# module_special_reg_ctrl.net
KiCad netlist of a schematic drawn in EAGLE
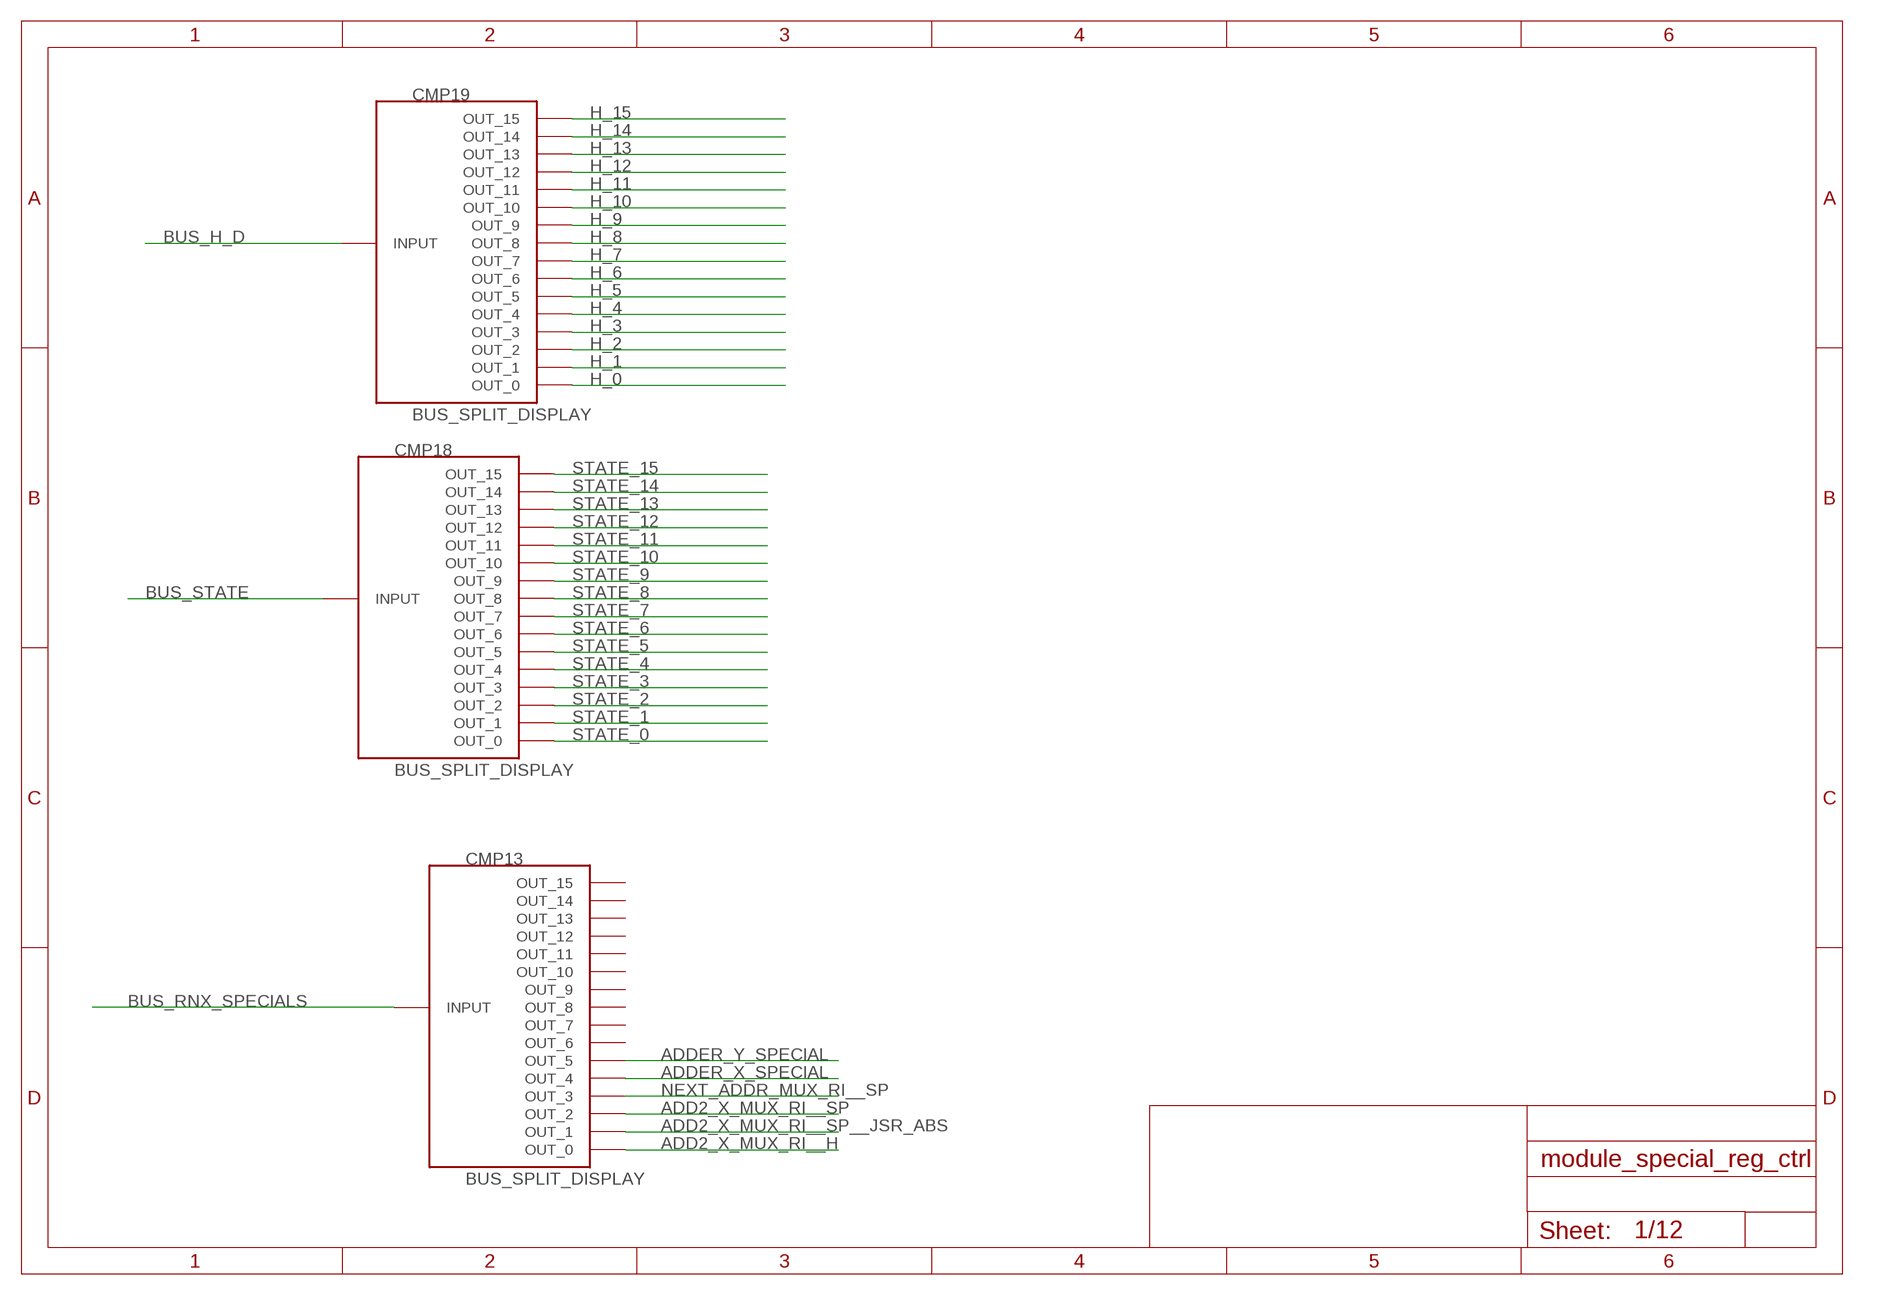
[diagram p0: schematic, sheet 1]
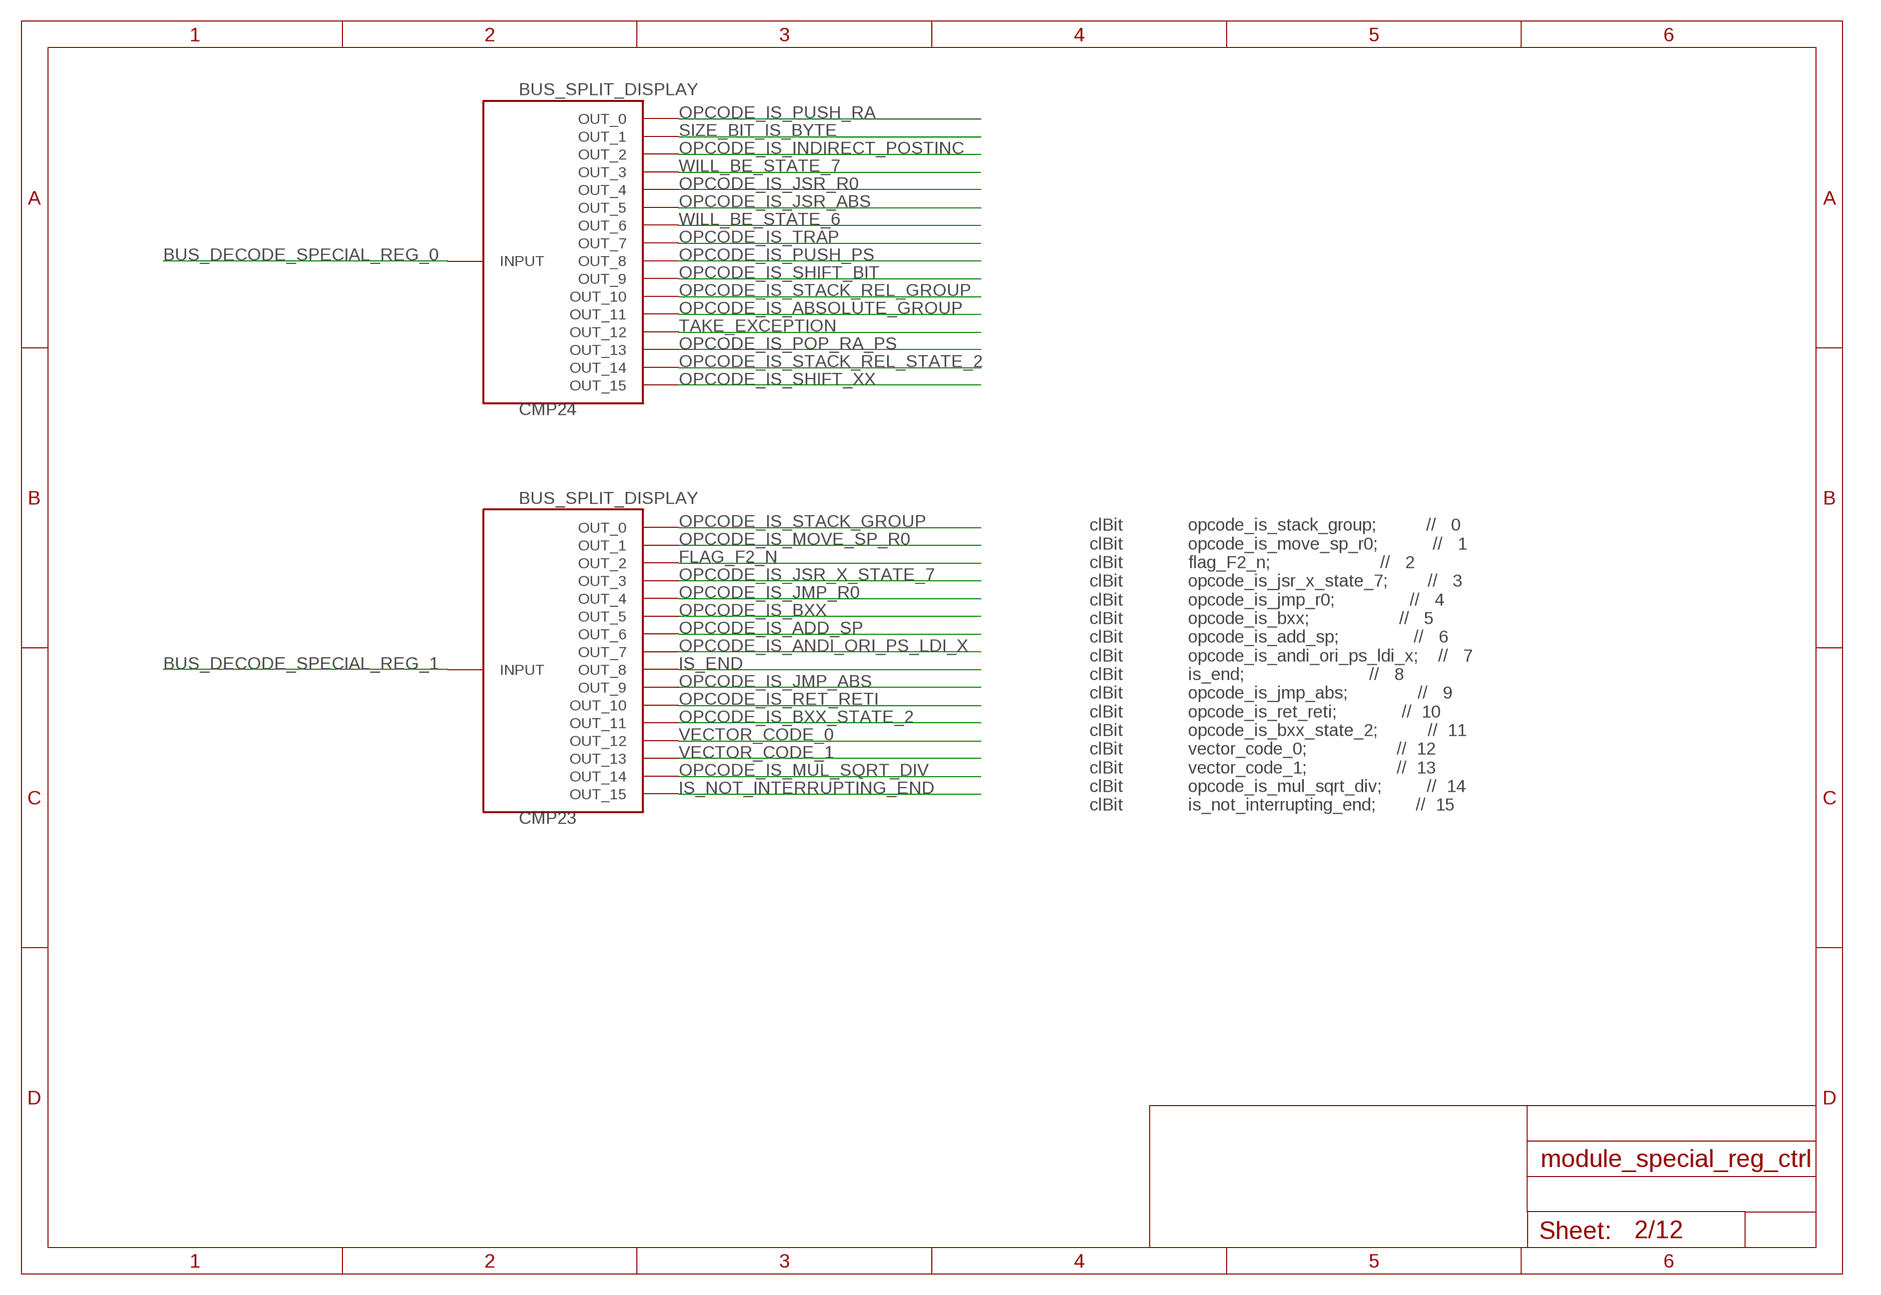
[diagram p1: schematic, sheet 2]
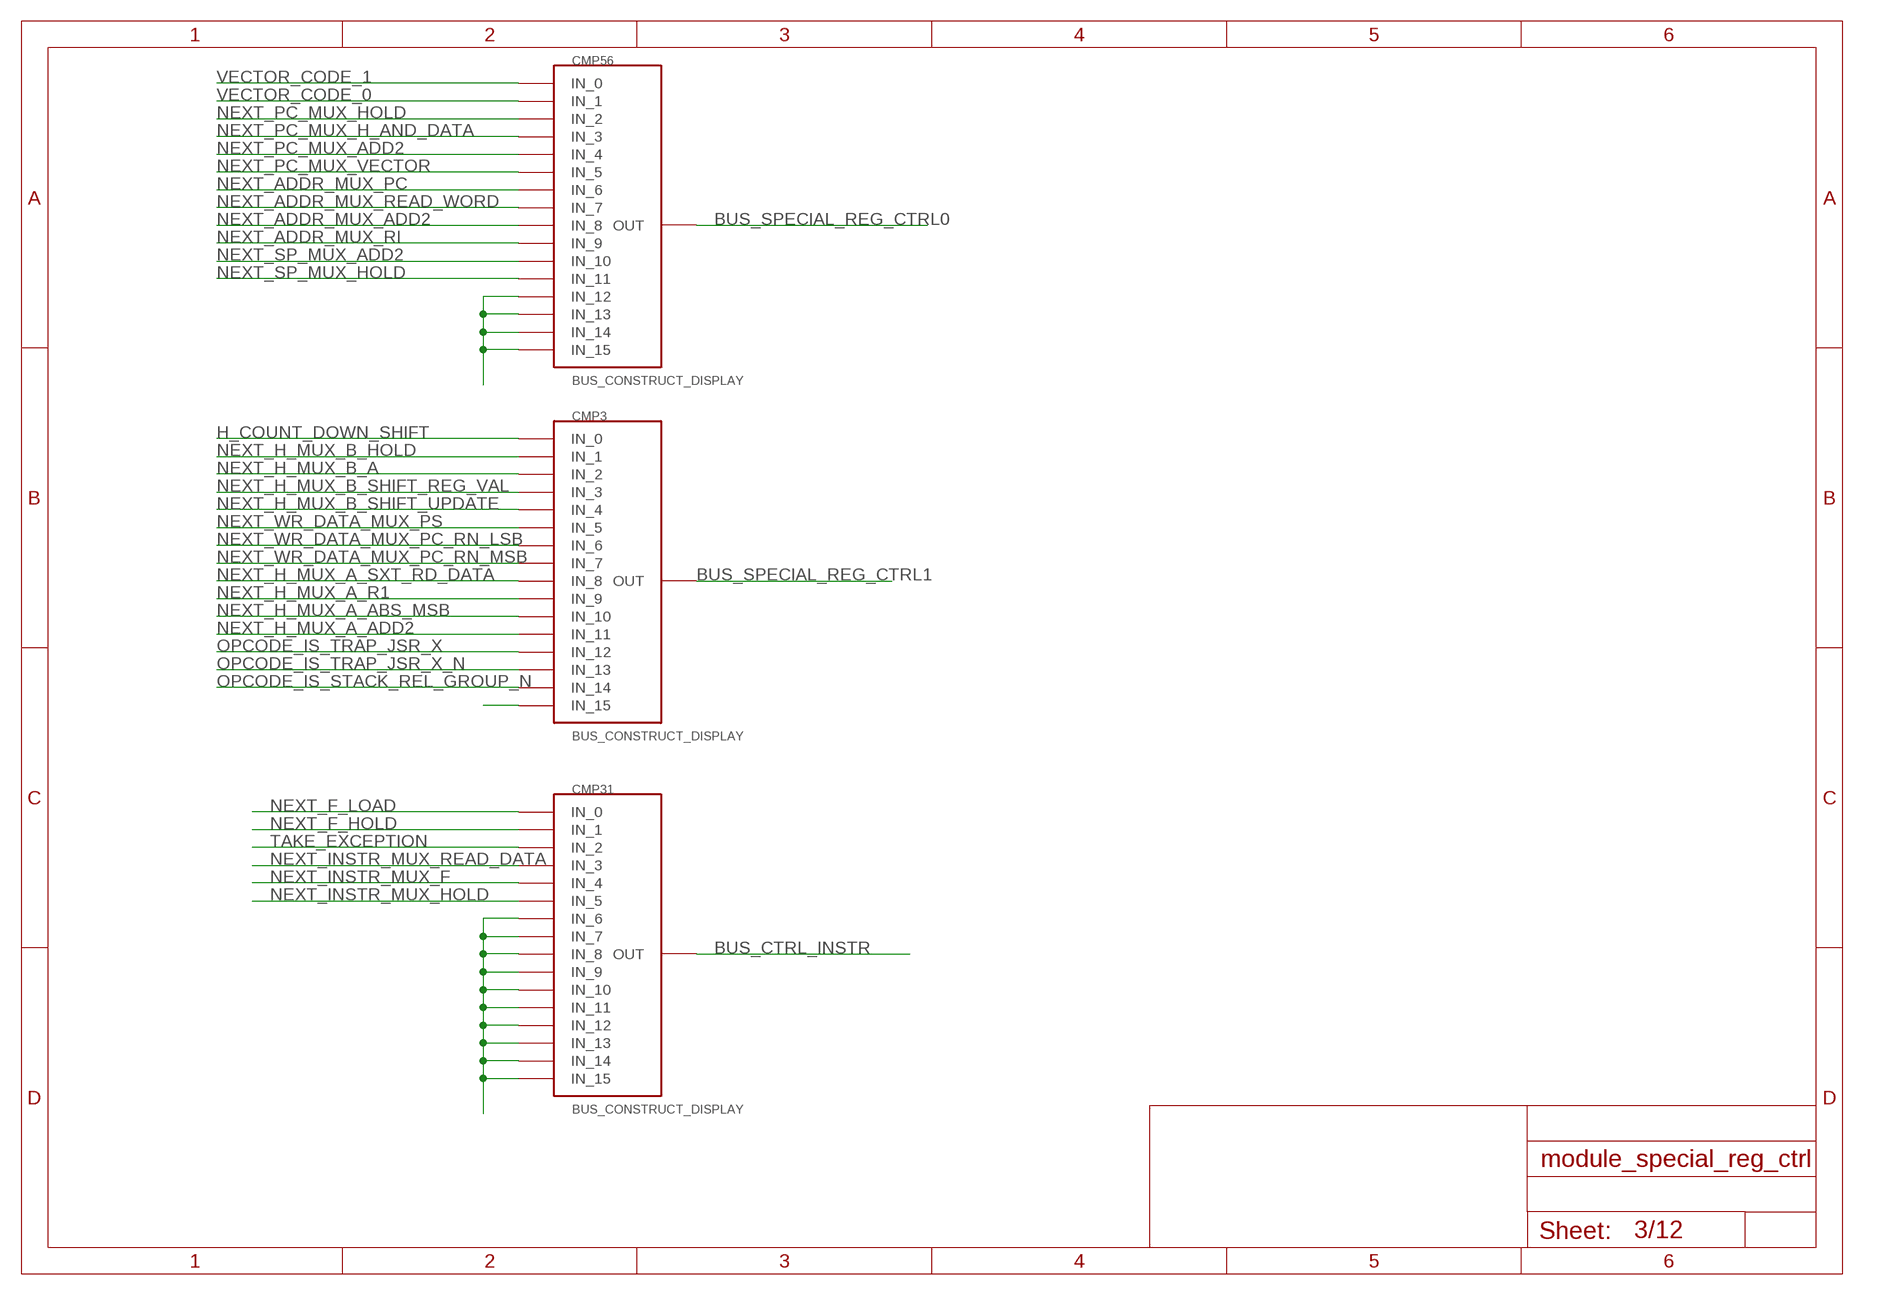
[diagram p2: schematic, sheet 3]
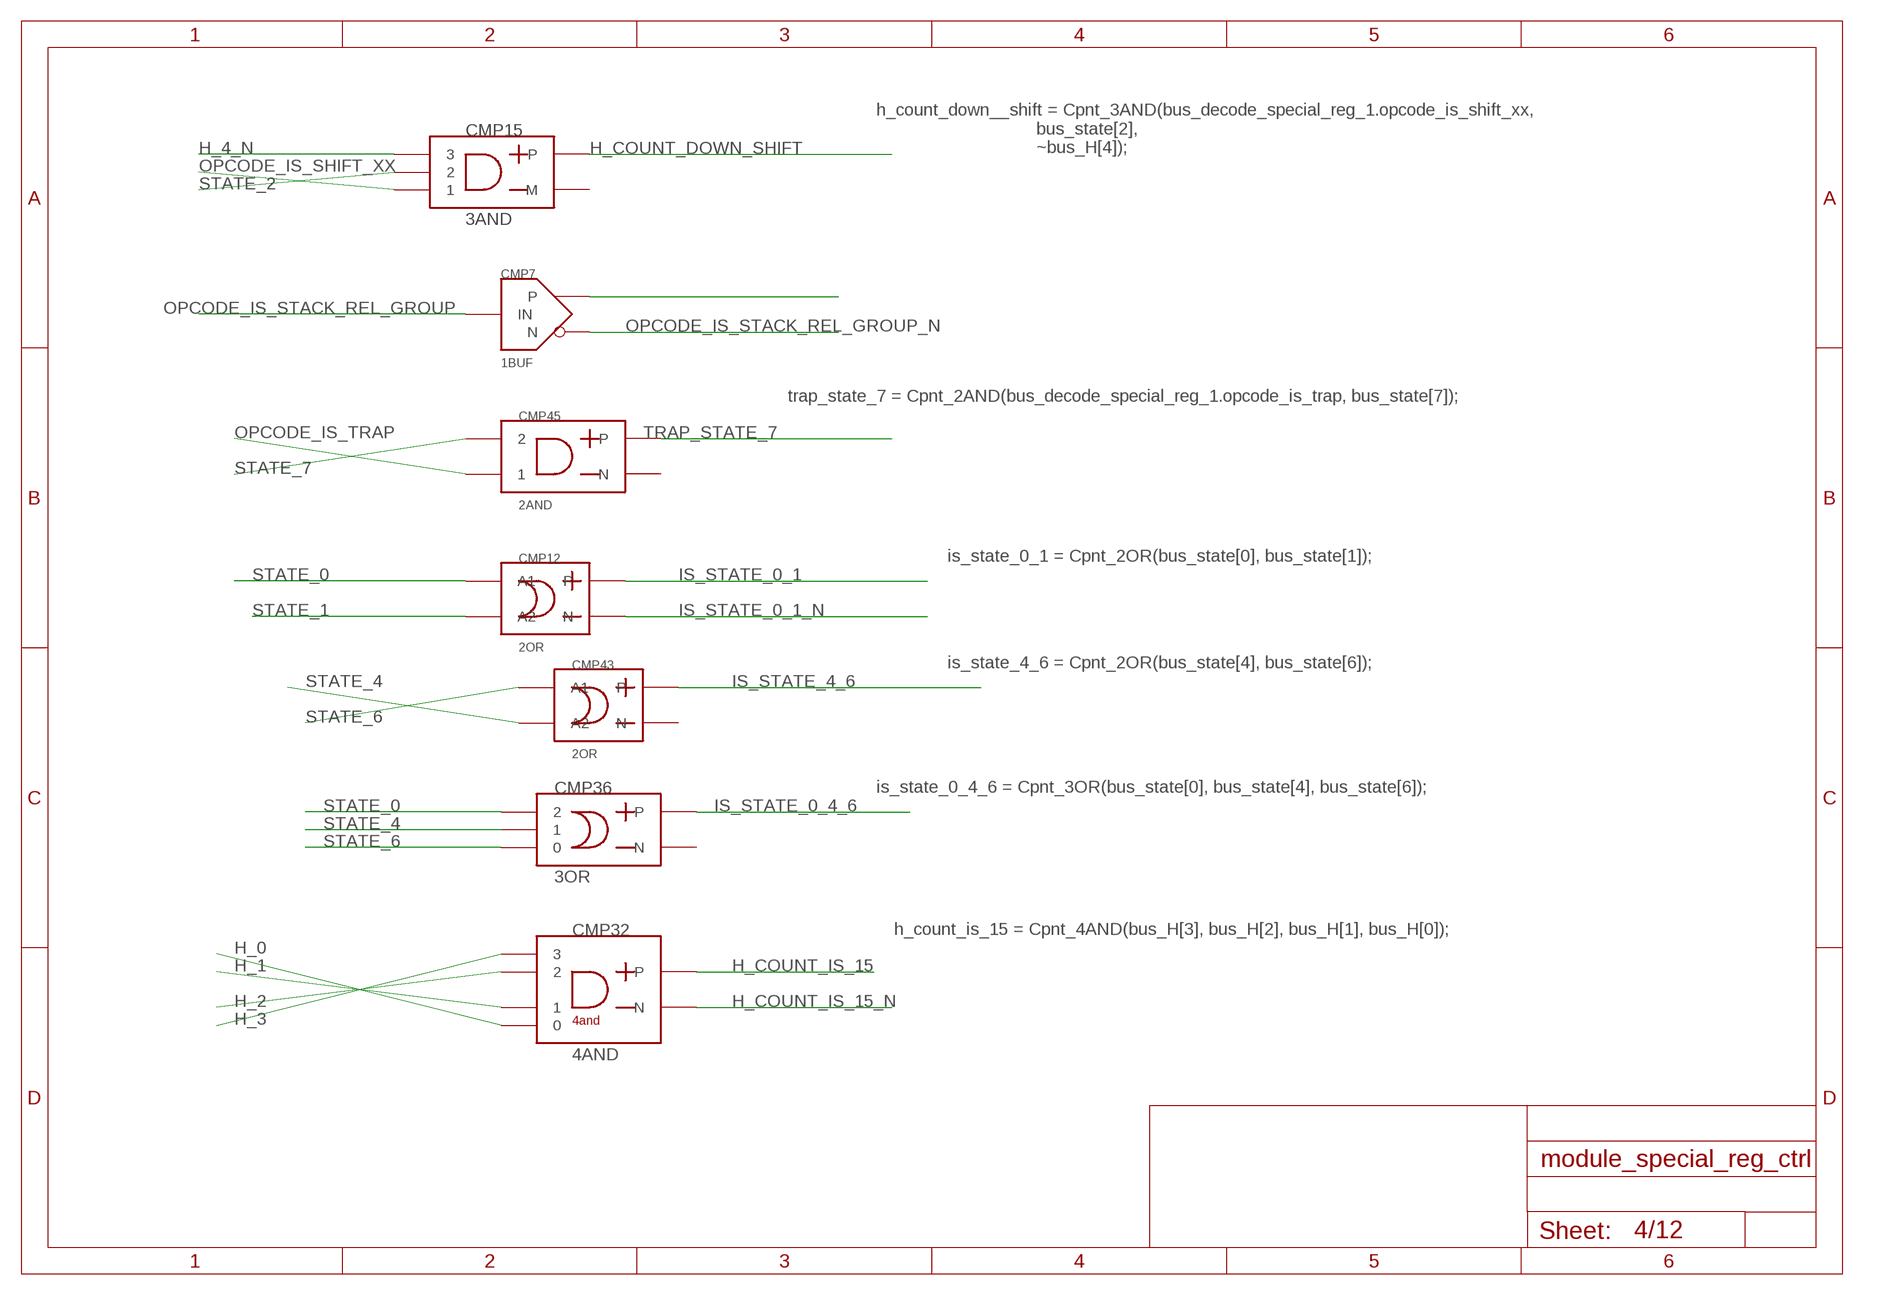
[diagram p3: schematic, sheet 4]
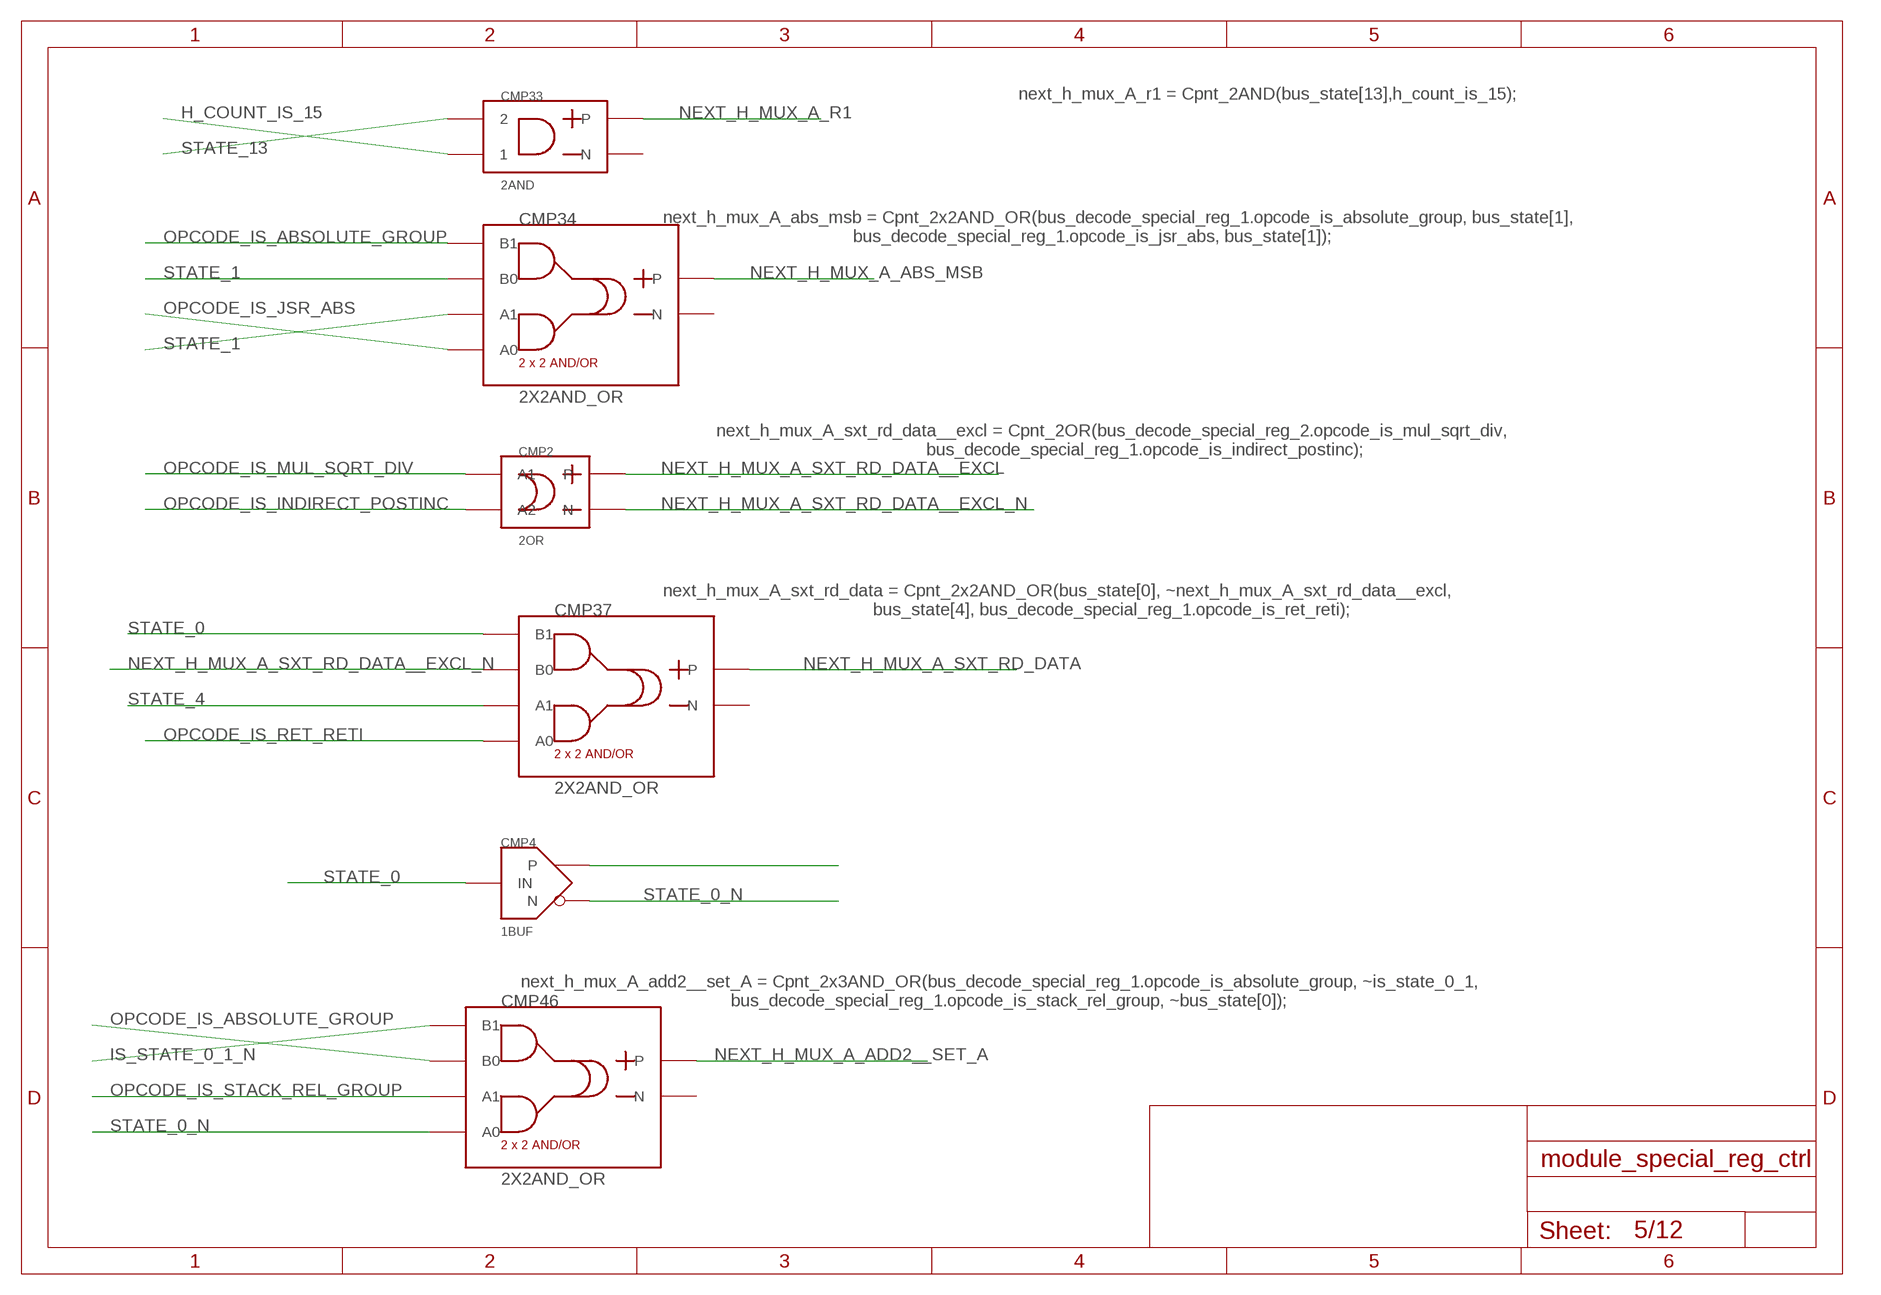
[diagram p4: schematic, sheet 5]
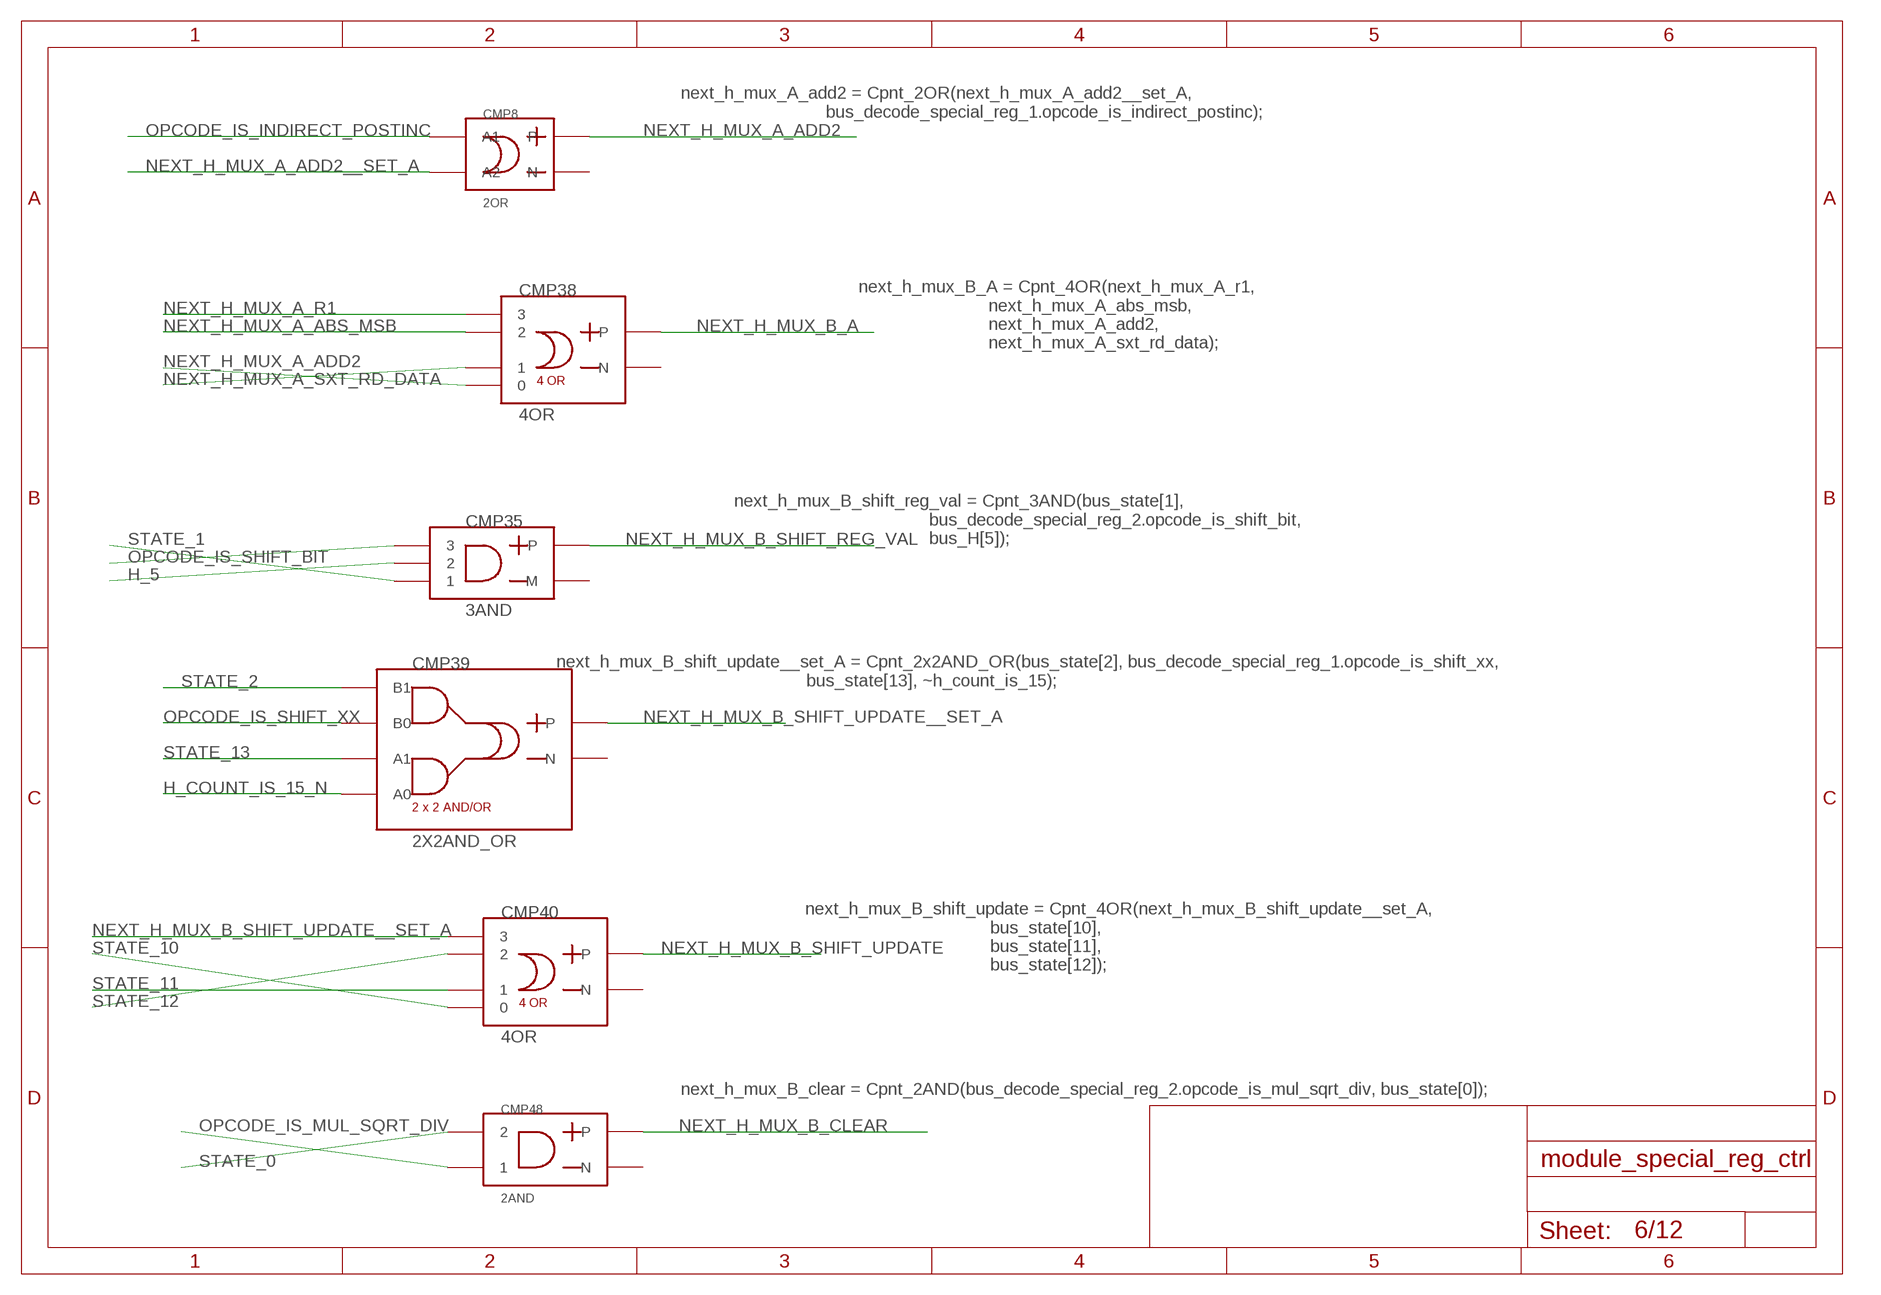
[diagram p5: schematic, sheet 6]
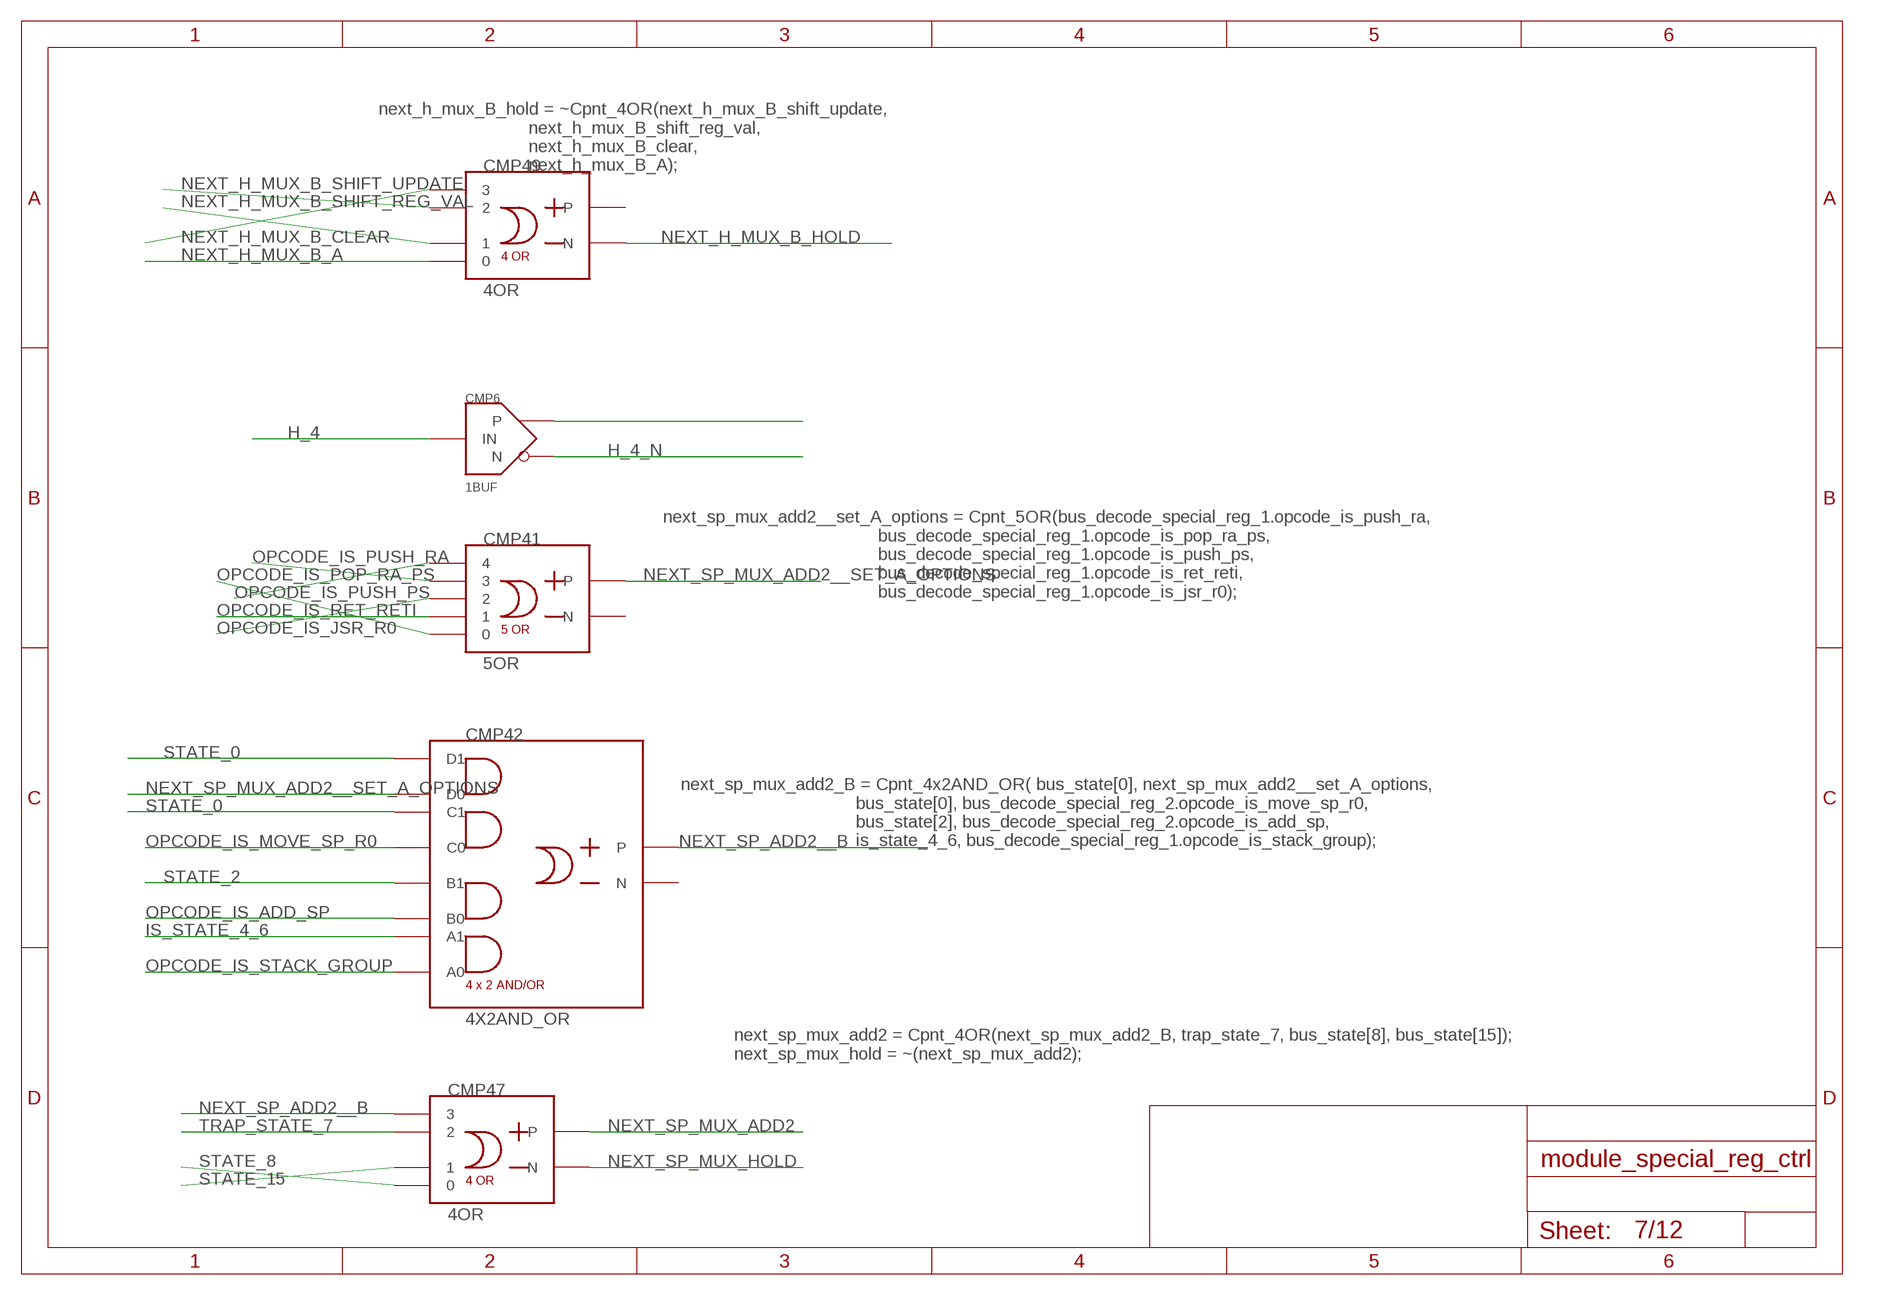
[diagram p6: schematic, sheet 7]
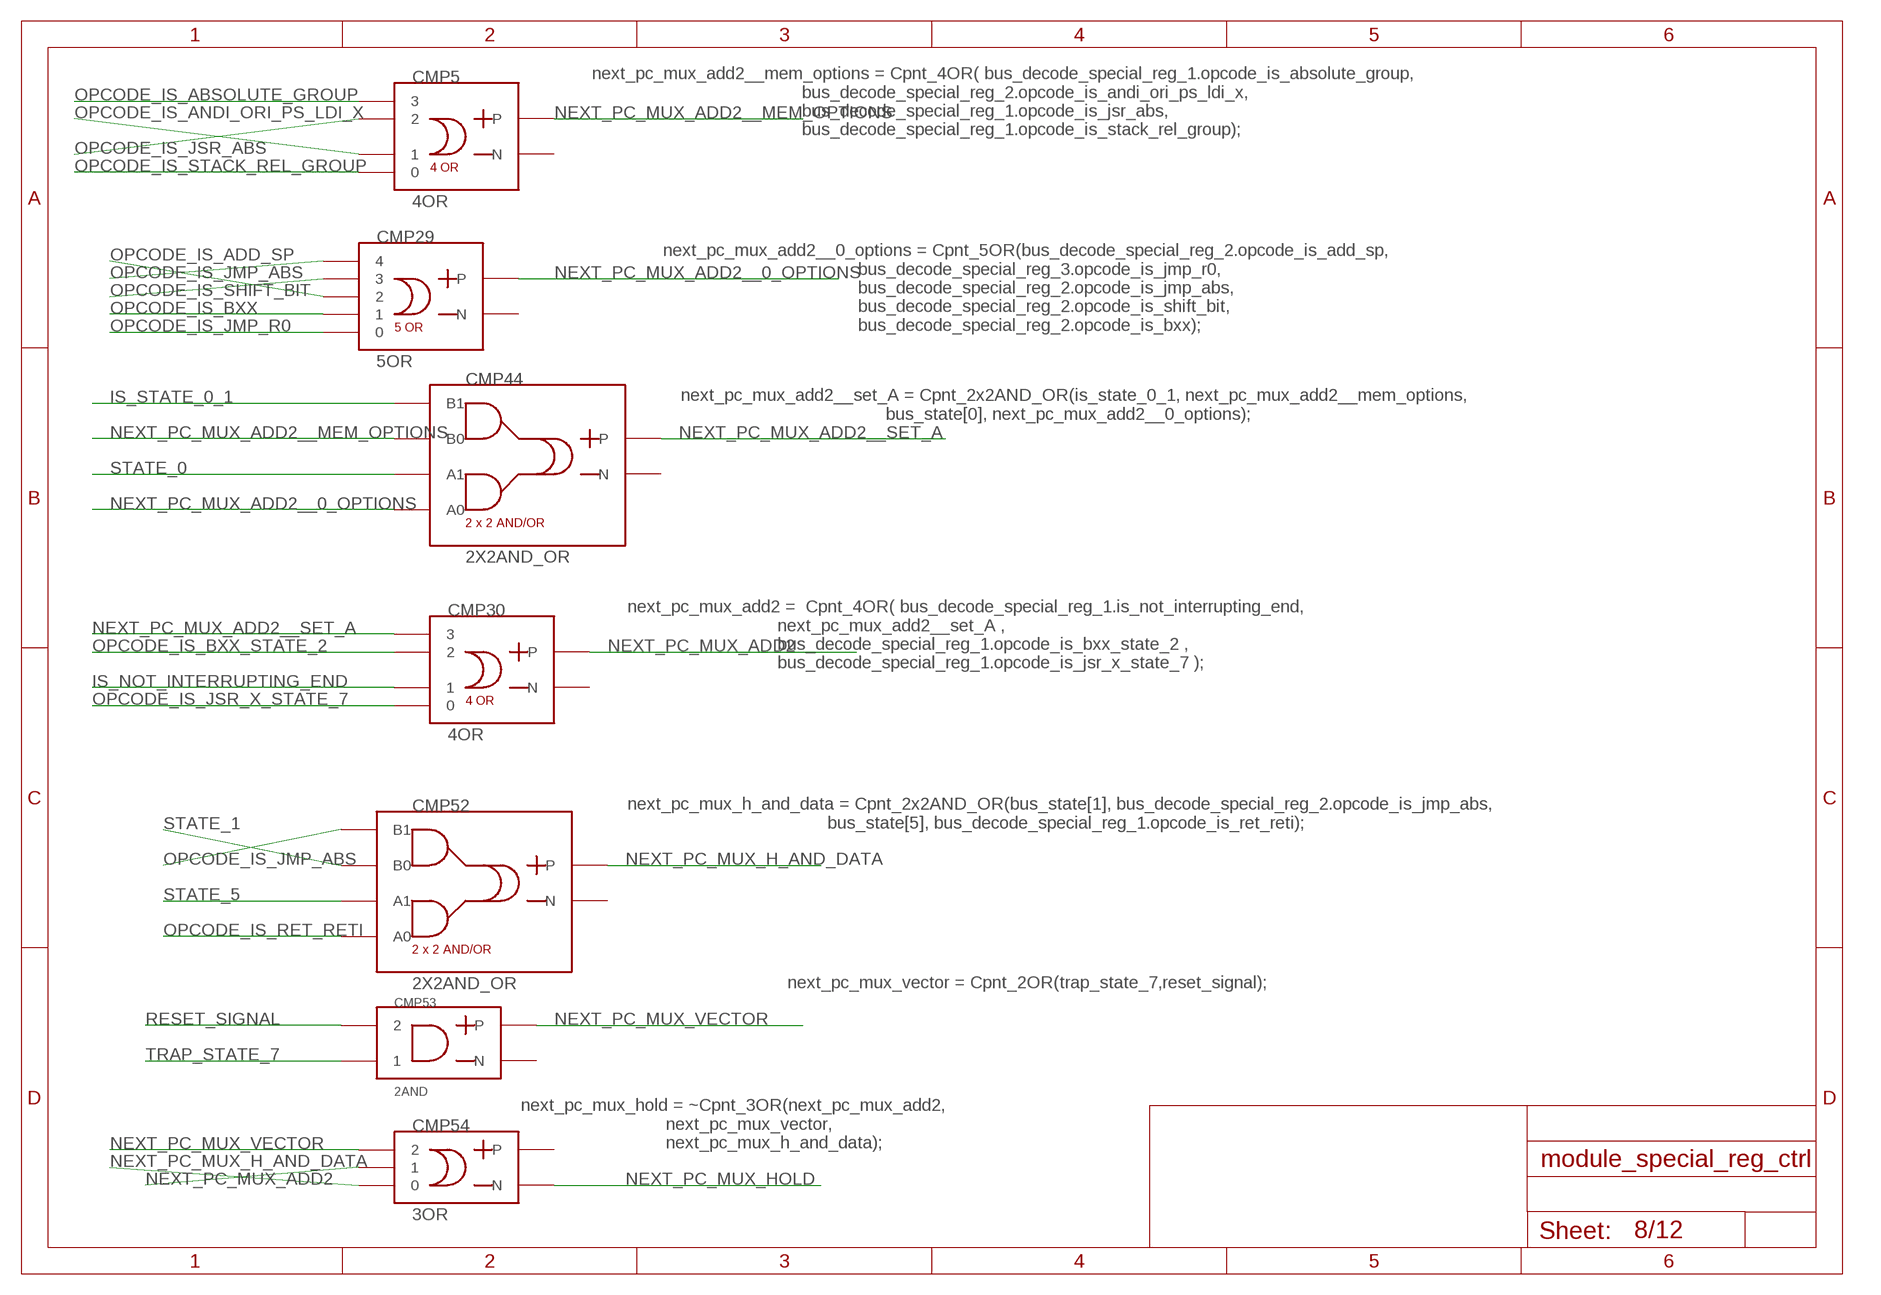
[diagram p7: schematic, sheet 8]
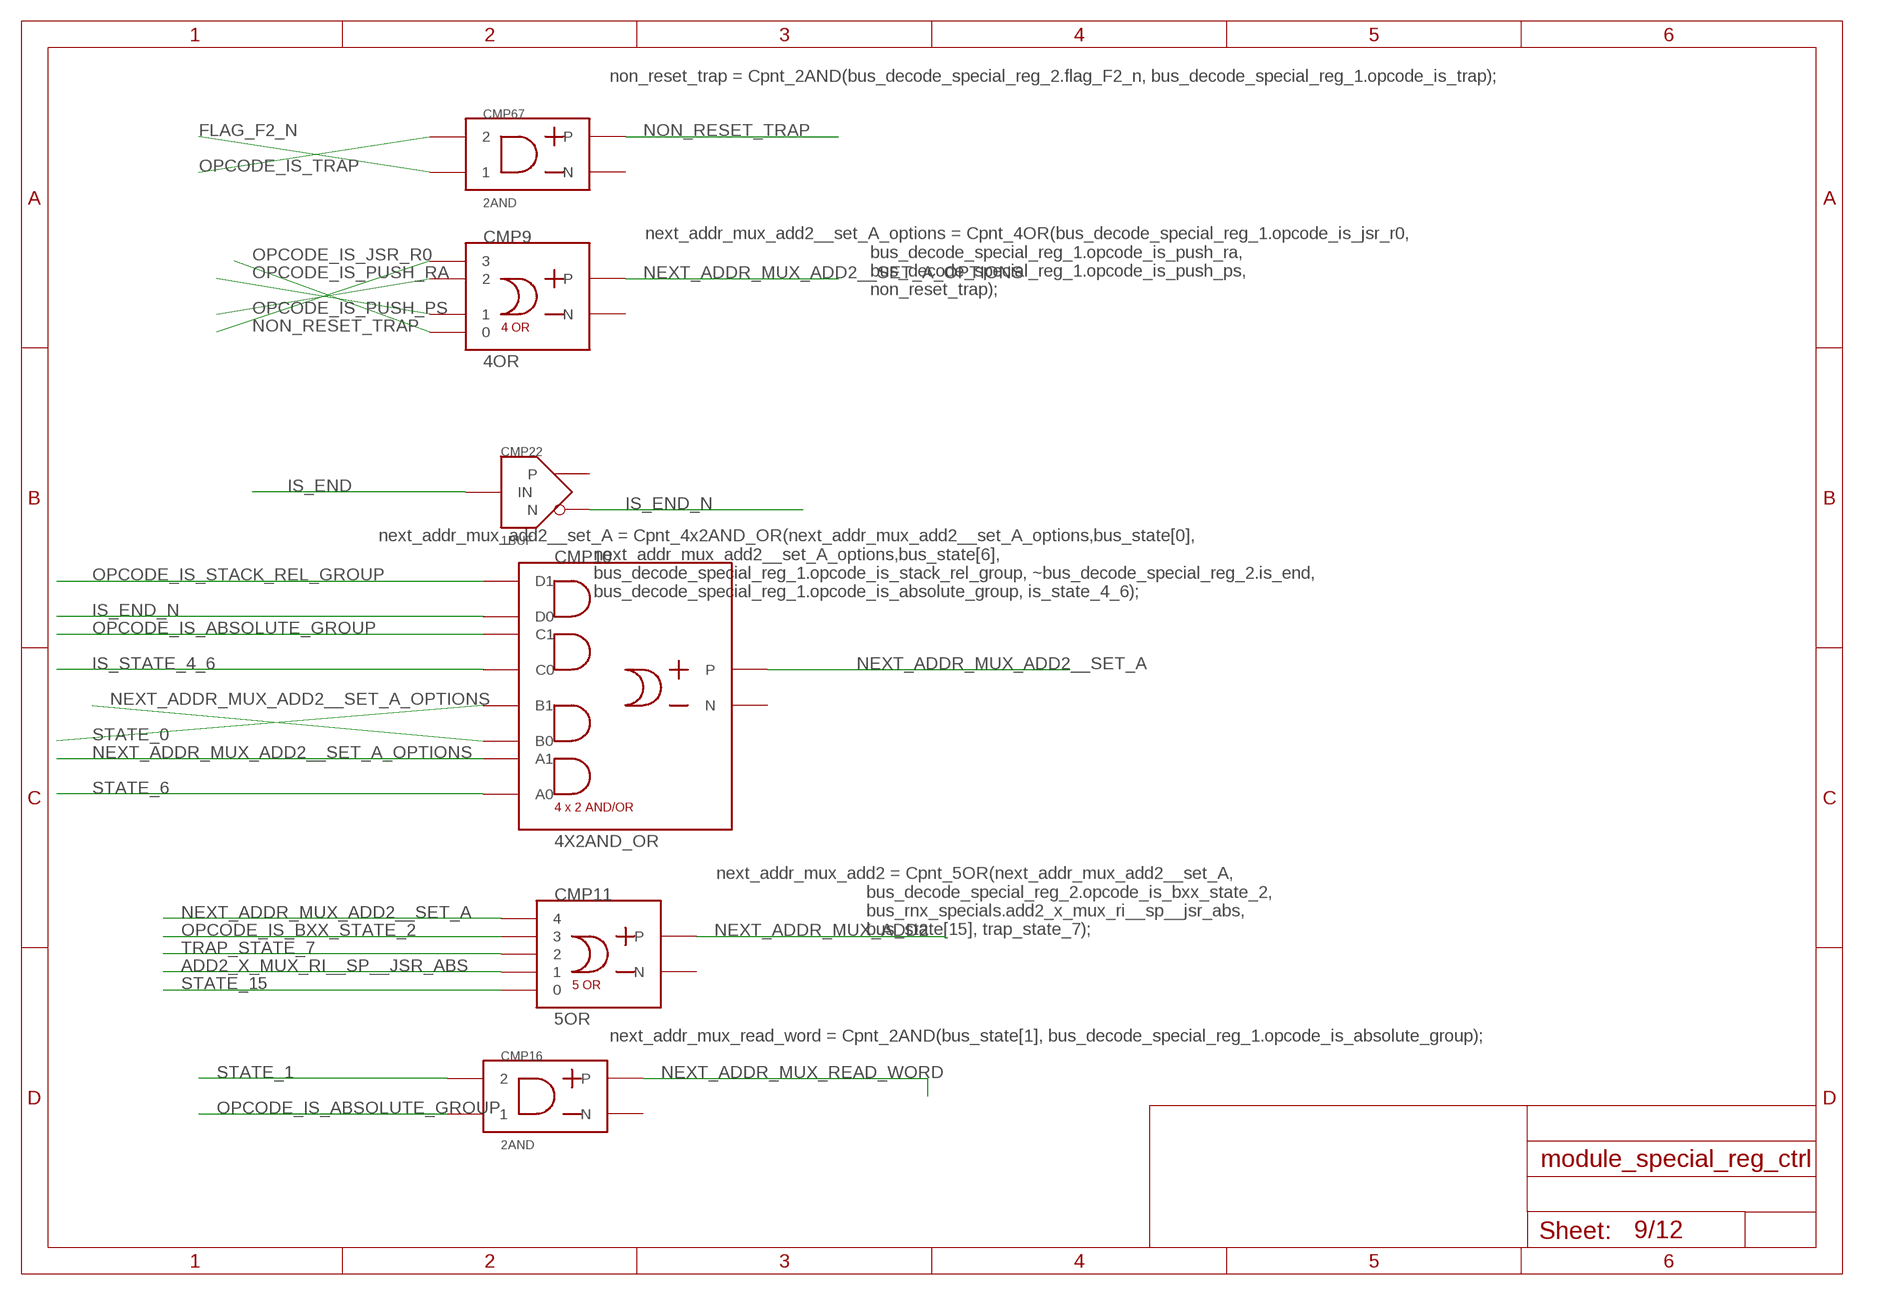
[diagram p8: schematic, sheet 9]
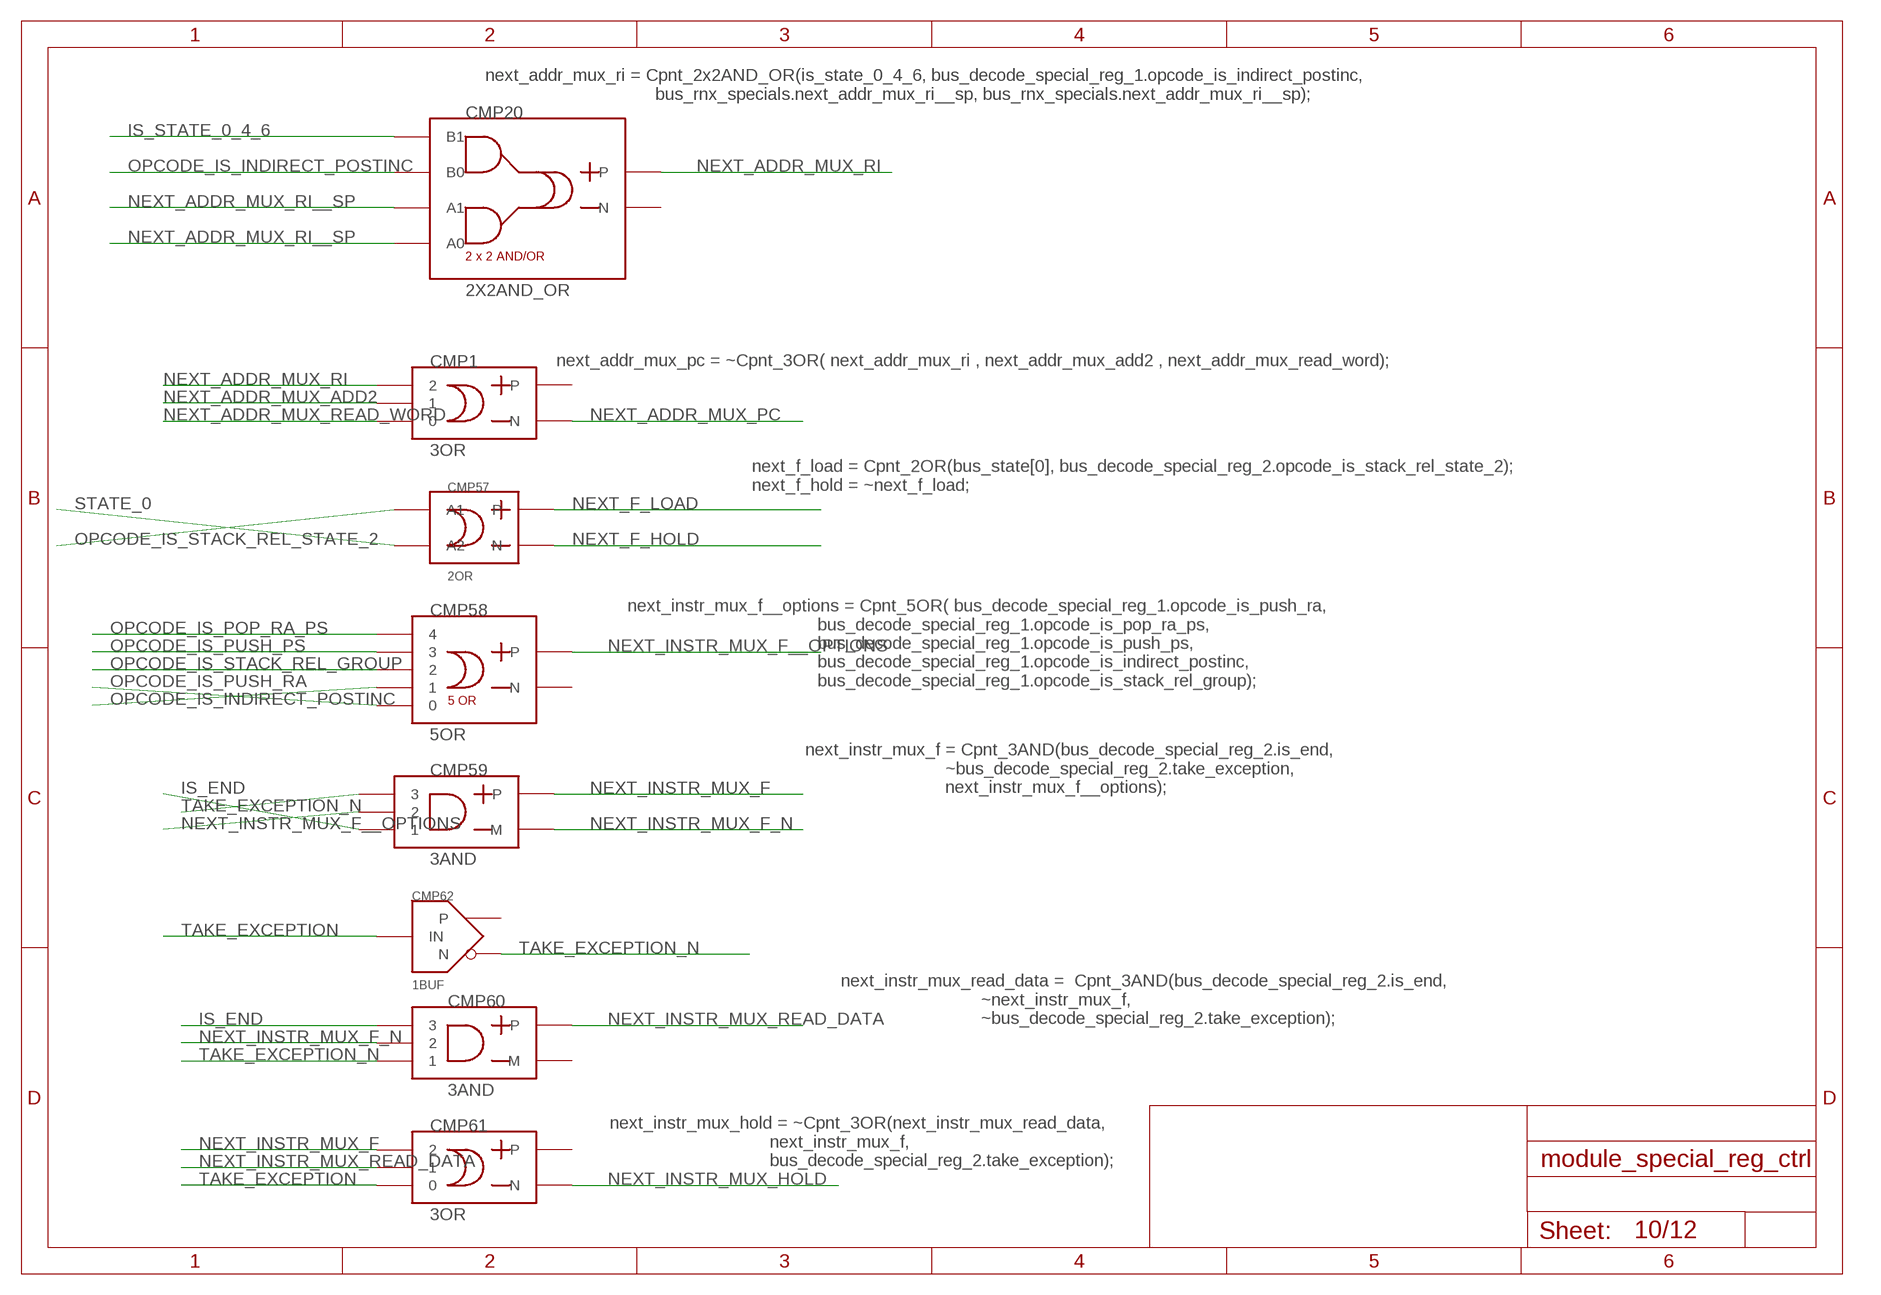
[diagram p9: schematic, sheet 10]
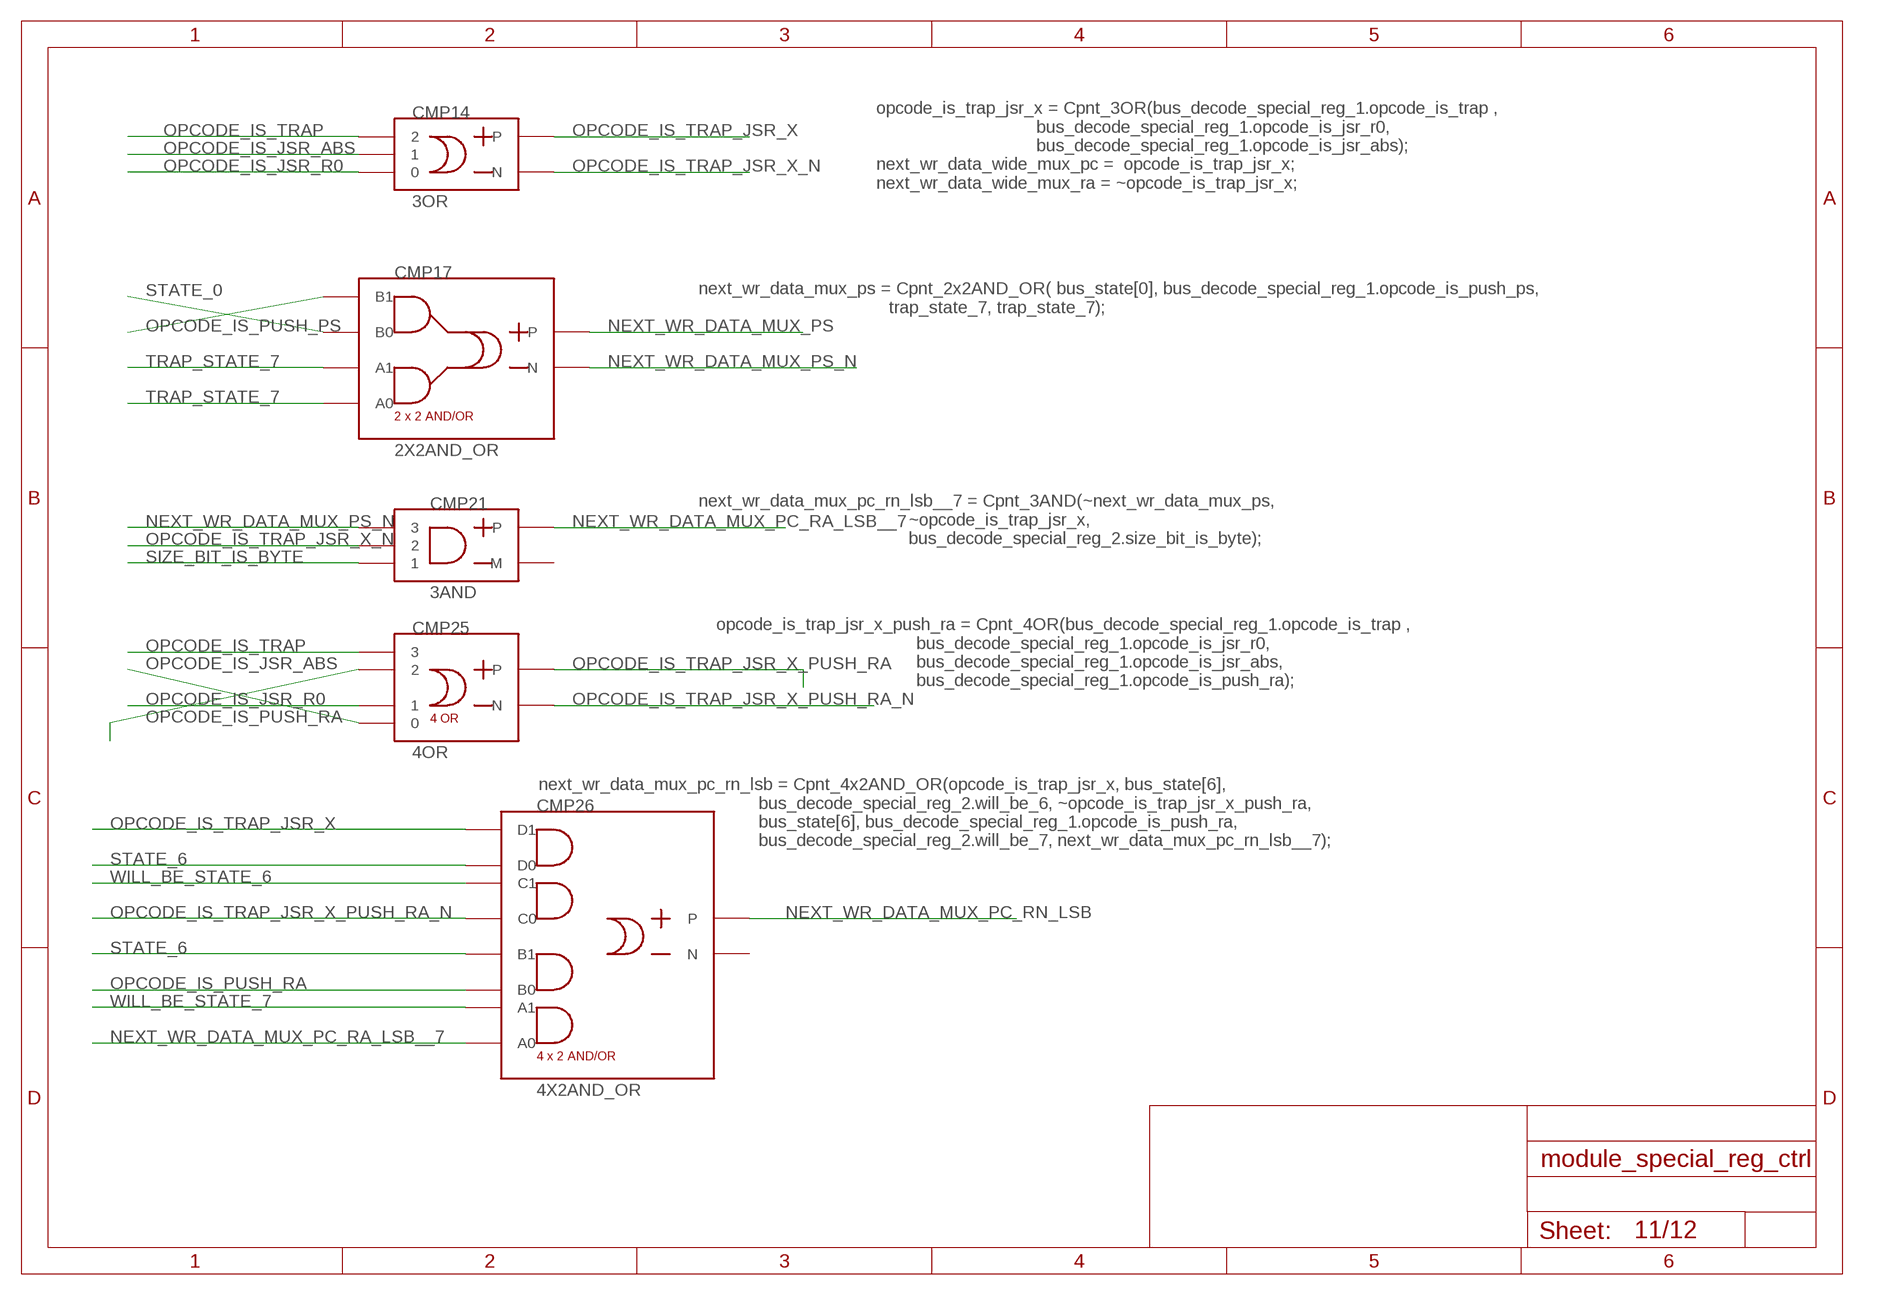
[diagram p10: schematic, sheet 11]
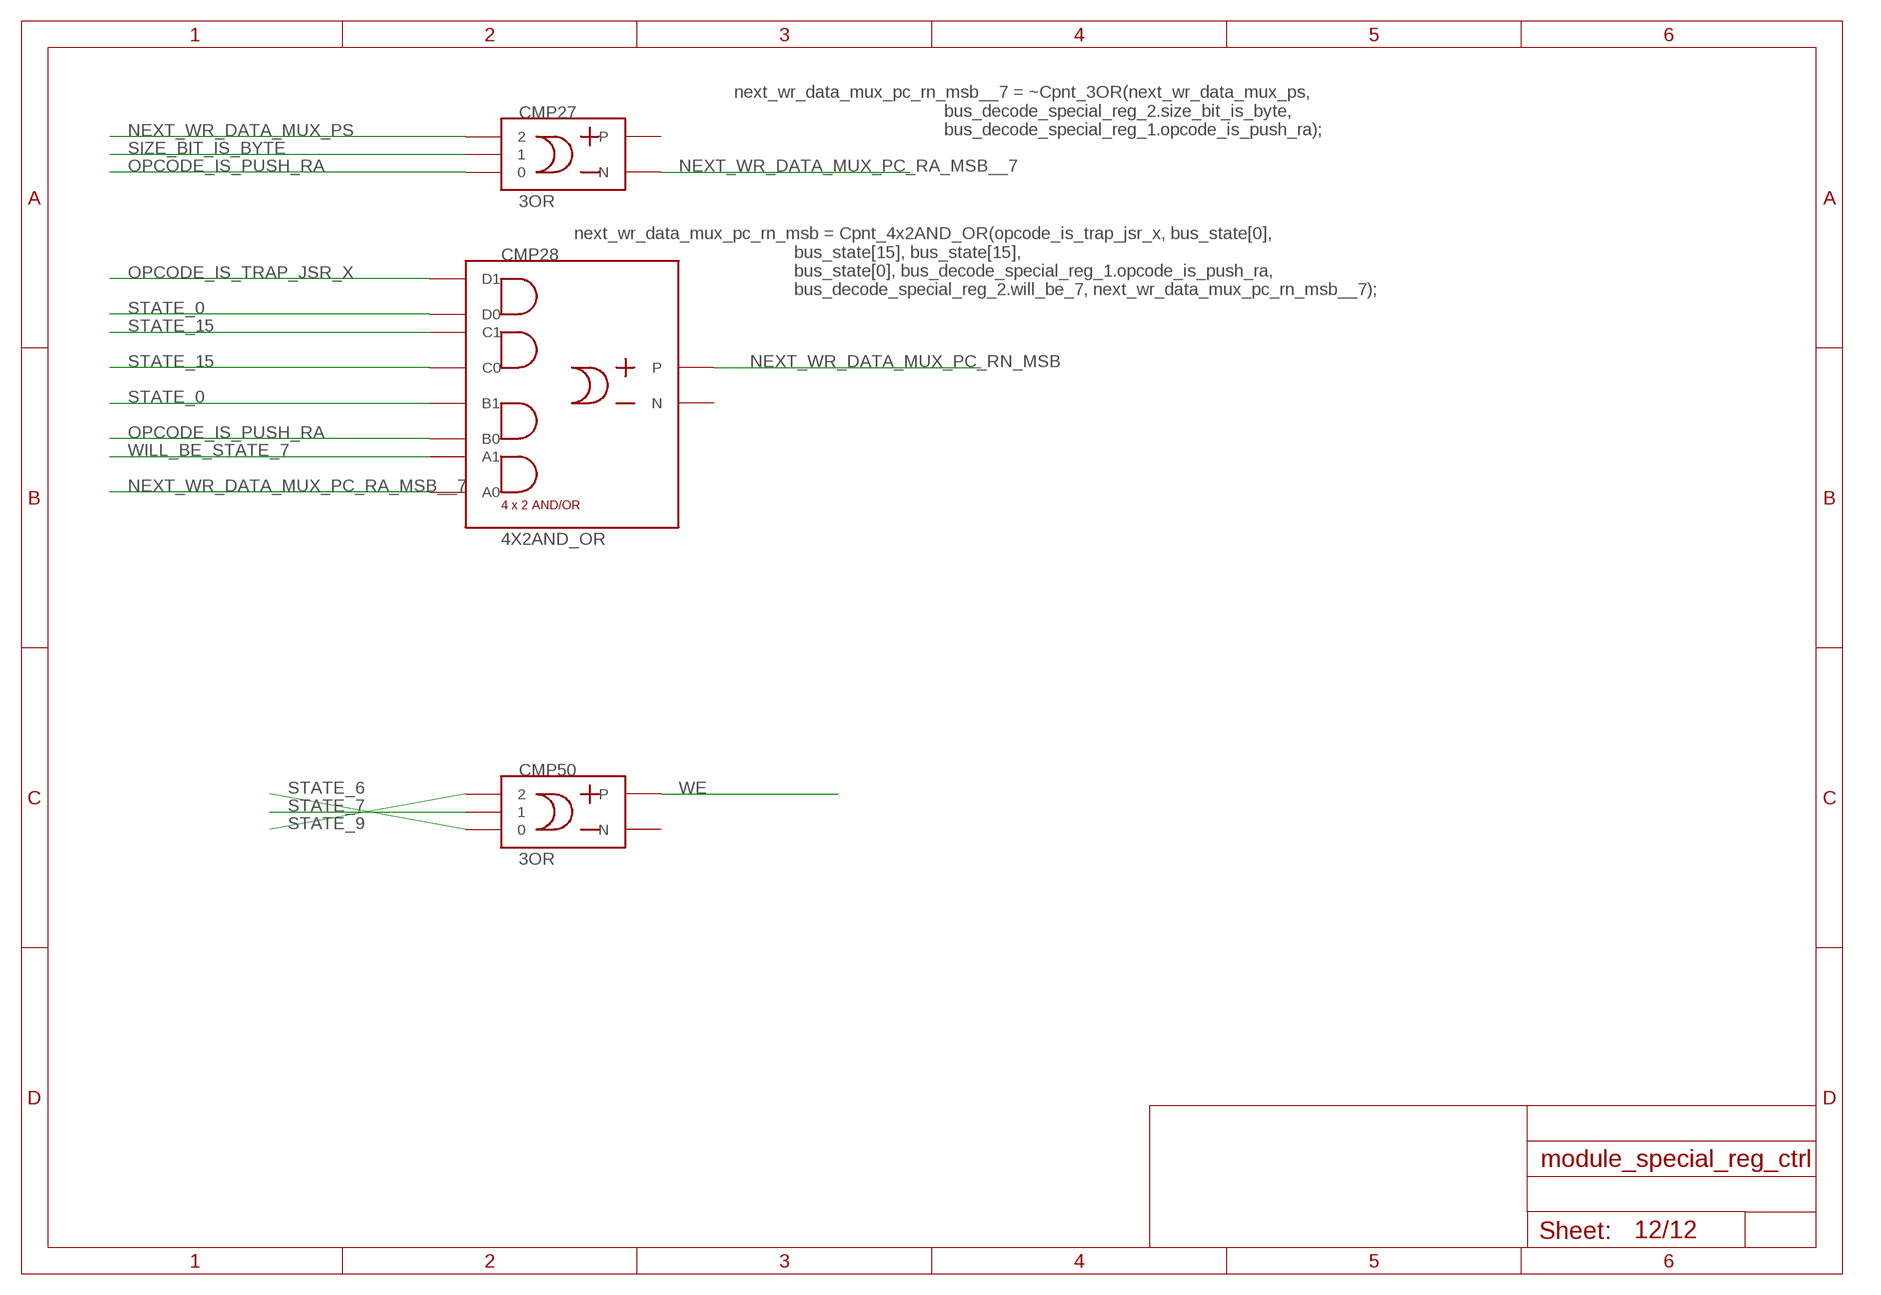
[diagram p11: schematic, sheet 12]

(export (version "E")
  (design (tool "Eeschema 10.0.6"))
  (components
    (comp (ref "CMP5")
      (value "4OR")
      (footprint "eagle-import:4OR")
      (libsource (lib "eagle-import") (part "4OR"))
    )
    (comp (ref "CMP29")
      (value "5OR")
      (footprint "eagle-import:5OR")
      (libsource (lib "eagle-import") (part "5OR"))
    )
    (comp (ref "CMP30")
      (value "4OR")
      (footprint "eagle-import:4OR")
      (libsource (lib "eagle-import") (part "4OR"))
    )
    (comp (ref "CMP44")
      (value "2X2AND_OR")
      (footprint "eagle-import:2X2AND_OR")
      (libsource (lib "eagle-import") (part "2X2AND_OR"))
    )
    (comp (ref "CMP52")
      (value "2X2AND_OR")
      (footprint "eagle-import:2X2AND_OR")
      (libsource (lib "eagle-import") (part "2X2AND_OR"))
    )
    (comp (ref "CMP53")
      (value "2AND")
      (footprint "eagle-import:2AND")
      (libsource (lib "eagle-import") (part "2AND"))
    )
    (comp (ref "CMP54")
      (value "3OR")
      (footprint "eagle-import:3OR")
      (libsource (lib "eagle-import") (part "3OR"))
    )
    (comp (ref "CMP14")
      (value "3OR")
      (footprint "eagle-import:3OR")
      (libsource (lib "eagle-import") (part "3OR"))
    )
    (comp (ref "CMP17")
      (value "2X2AND_OR")
      (footprint "eagle-import:2X2AND_OR")
      (libsource (lib "eagle-import") (part "2X2AND_OR"))
    )
    (comp (ref "CMP21")
      (value "3AND")
      (footprint "eagle-import:3AND")
      (libsource (lib "eagle-import") (part "3AND"))
    )
    (comp (ref "CMP25")
      (value "4OR")
      (footprint "eagle-import:4OR")
      (libsource (lib "eagle-import") (part "4OR"))
    )
    (comp (ref "CMP26")
      (value "4X2AND_OR")
      (footprint "eagle-import:4X2AND_OR")
      (libsource (lib "eagle-import") (part "4X2AND_OR"))
    )
    (comp (ref "CMP13")
      (value "BUS_SPLIT_DISPLAY")
      (footprint "eagle-import:BUS_SPLIT_DISPLAY")
      (libsource (lib "eagle-import") (part "BUS_SPLIT_DISPLAY"))
    )
    (comp (ref "CMP18")
      (value "BUS_SPLIT_DISPLAY")
      (footprint "eagle-import:BUS_SPLIT_DISPLAY")
      (libsource (lib "eagle-import") (part "BUS_SPLIT_DISPLAY"))
    )
    (comp (ref "CMP19")
      (value "BUS_SPLIT_DISPLAY")
      (footprint "eagle-import:BUS_SPLIT_DISPLAY")
      (libsource (lib "eagle-import") (part "BUS_SPLIT_DISPLAY"))
    )
    (comp (ref "CMP8")
      (value "2OR")
      (footprint "eagle-import:2OR")
      (libsource (lib "eagle-import") (part "2OR"))
    )
    (comp (ref "CMP35")
      (value "3AND")
      (footprint "eagle-import:3AND")
      (libsource (lib "eagle-import") (part "3AND"))
    )
    (comp (ref "CMP38")
      (value "4OR")
      (footprint "eagle-import:4OR")
      (libsource (lib "eagle-import") (part "4OR"))
    )
    (comp (ref "CMP39")
      (value "2X2AND_OR")
      (footprint "eagle-import:2X2AND_OR")
      (libsource (lib "eagle-import") (part "2X2AND_OR"))
    )
    (comp (ref "CMP40")
      (value "4OR")
      (footprint "eagle-import:4OR")
      (libsource (lib "eagle-import") (part "4OR"))
    )
    (comp (ref "CMP48")
      (value "2AND")
      (footprint "eagle-import:2AND")
      (libsource (lib "eagle-import") (part "2AND"))
    )
    (comp (ref "CMP23")
      (value "BUS_SPLIT_DISPLAY")
      (footprint "eagle-import:BUS_SPLIT_DISPLAY")
      (libsource (lib "eagle-import") (part "BUS_SPLIT_DISPLAY"))
    )
    (comp (ref "CMP24")
      (value "BUS_SPLIT_DISPLAY")
      (footprint "eagle-import:BUS_SPLIT_DISPLAY")
      (libsource (lib "eagle-import") (part "BUS_SPLIT_DISPLAY"))
    )
    (comp (ref "CMP3")
      (value "BUS_CONSTRUCT_DISPLAY")
      (footprint "eagle-import:BUS_SPLIT_DISPLAY")
      (libsource (lib "eagle-import") (part "BUS_CONSTRUCT_DISPLAY"))
    )
    (comp (ref "CMP31")
      (value "BUS_CONSTRUCT_DISPLAY")
      (footprint "eagle-import:BUS_SPLIT_DISPLAY")
      (libsource (lib "eagle-import") (part "BUS_CONSTRUCT_DISPLAY"))
    )
    (comp (ref "CMP56")
      (value "BUS_CONSTRUCT_DISPLAY")
      (footprint "eagle-import:BUS_SPLIT_DISPLAY")
      (libsource (lib "eagle-import") (part "BUS_CONSTRUCT_DISPLAY"))
    )
    (comp (ref "CMP7")
      (value "1BUF")
      (footprint "eagle-import:1BUF")
      (libsource (lib "eagle-import") (part "1BUF"))
    )
    (comp (ref "CMP12")
      (value "2OR")
      (footprint "eagle-import:2OR")
      (libsource (lib "eagle-import") (part "2OR"))
    )
    (comp (ref "CMP15")
      (value "3AND")
      (footprint "eagle-import:3AND")
      (libsource (lib "eagle-import") (part "3AND"))
    )
    (comp (ref "CMP32")
      (value "4AND")
      (footprint "eagle-import:4AND")
      (libsource (lib "eagle-import") (part "4AND"))
    )
    (comp (ref "CMP36")
      (value "3OR")
      (footprint "eagle-import:3OR")
      (libsource (lib "eagle-import") (part "3OR"))
    )
    (comp (ref "CMP43")
      (value "2OR")
      (footprint "eagle-import:2OR")
      (libsource (lib "eagle-import") (part "2OR"))
    )
    (comp (ref "CMP45")
      (value "2AND")
      (footprint "eagle-import:2AND")
      (libsource (lib "eagle-import") (part "2AND"))
    )
    (comp (ref "CMP27")
      (value "3OR")
      (footprint "eagle-import:3OR")
      (libsource (lib "eagle-import") (part "3OR"))
    )
    (comp (ref "CMP28")
      (value "4X2AND_OR")
      (footprint "eagle-import:4X2AND_OR")
      (libsource (lib "eagle-import") (part "4X2AND_OR"))
    )
    (comp (ref "CMP50")
      (value "3OR")
      (footprint "eagle-import:3OR")
      (libsource (lib "eagle-import") (part "3OR"))
    )
    (comp (ref "CMP6")
      (value "1BUF")
      (footprint "eagle-import:1BUF")
      (libsource (lib "eagle-import") (part "1BUF"))
    )
    (comp (ref "CMP41")
      (value "5OR")
      (footprint "eagle-import:5OR")
      (libsource (lib "eagle-import") (part "5OR"))
    )
    (comp (ref "CMP42")
      (value "4X2AND_OR")
      (footprint "eagle-import:4X2AND_OR")
      (libsource (lib "eagle-import") (part "4X2AND_OR"))
    )
    (comp (ref "CMP47")
      (value "4OR")
      (footprint "eagle-import:4OR")
      (libsource (lib "eagle-import") (part "4OR"))
    )
    (comp (ref "CMP49")
      (value "4OR")
      (footprint "eagle-import:4OR")
      (libsource (lib "eagle-import") (part "4OR"))
    )
    (comp (ref "CMP9")
      (value "4OR")
      (footprint "eagle-import:4OR")
      (libsource (lib "eagle-import") (part "4OR"))
    )
    (comp (ref "CMP10")
      (value "4X2AND_OR")
      (footprint "eagle-import:4X2AND_OR")
      (libsource (lib "eagle-import") (part "4X2AND_OR"))
    )
    (comp (ref "CMP11")
      (value "5OR")
      (footprint "eagle-import:5OR")
      (libsource (lib "eagle-import") (part "5OR"))
    )
    (comp (ref "CMP16")
      (value "2AND")
      (footprint "eagle-import:2AND")
      (libsource (lib "eagle-import") (part "2AND"))
    )
    (comp (ref "CMP22")
      (value "1BUF")
      (footprint "eagle-import:1BUF")
      (libsource (lib "eagle-import") (part "1BUF"))
    )
    (comp (ref "CMP67")
      (value "2AND")
      (footprint "eagle-import:2AND")
      (libsource (lib "eagle-import") (part "2AND"))
    )
    (comp (ref "CMP1")
      (value "3OR")
      (footprint "eagle-import:3OR")
      (libsource (lib "eagle-import") (part "3OR"))
    )
    (comp (ref "CMP20")
      (value "2X2AND_OR")
      (footprint "eagle-import:2X2AND_OR")
      (libsource (lib "eagle-import") (part "2X2AND_OR"))
    )
    (comp (ref "CMP57")
      (value "2OR")
      (footprint "eagle-import:2OR")
      (libsource (lib "eagle-import") (part "2OR"))
    )
    (comp (ref "CMP58")
      (value "5OR")
      (footprint "eagle-import:5OR")
      (libsource (lib "eagle-import") (part "5OR"))
    )
    (comp (ref "CMP59")
      (value "3AND")
      (footprint "eagle-import:3AND")
      (libsource (lib "eagle-import") (part "3AND"))
    )
    (comp (ref "CMP60")
      (value "3AND")
      (footprint "eagle-import:3AND")
      (libsource (lib "eagle-import") (part "3AND"))
    )
    (comp (ref "CMP61")
      (value "3OR")
      (footprint "eagle-import:3OR")
      (libsource (lib "eagle-import") (part "3OR"))
    )
    (comp (ref "CMP62")
      (value "1BUF")
      (footprint "eagle-import:1BUF")
      (libsource (lib "eagle-import") (part "1BUF"))
    )
    (comp (ref "CMP2")
      (value "2OR")
      (footprint "eagle-import:2OR")
      (libsource (lib "eagle-import") (part "2OR"))
    )
    (comp (ref "CMP4")
      (value "1BUF")
      (footprint "eagle-import:1BUF")
      (libsource (lib "eagle-import") (part "1BUF"))
    )
    (comp (ref "CMP33")
      (value "2AND")
      (footprint "eagle-import:2AND")
      (libsource (lib "eagle-import") (part "2AND"))
    )
    (comp (ref "CMP34")
      (value "2X2AND_OR")
      (footprint "eagle-import:2X2AND_OR")
      (libsource (lib "eagle-import") (part "2X2AND_OR"))
    )
    (comp (ref "CMP37")
      (value "2X2AND_OR")
      (footprint "eagle-import:2X2AND_OR")
      (libsource (lib "eagle-import") (part "2X2AND_OR"))
    )
    (comp (ref "CMP46")
      (value "2X2AND_OR")
      (footprint "eagle-import:2X2AND_OR")
      (libsource (lib "eagle-import") (part "2X2AND_OR"))
    )
  )
  (nets
    (net (code "1") (name "ADD2_X_MUX_RI__H") (class "Default")
      (node (ref "CMP13") (pin "P$1") (pinfunction "OUT_0_P$1") (pintype "output"))
    )
    (net (code "2") (name "ADD2_X_MUX_RI__SP") (class "Default")
      (node (ref "CMP13") (pin "P$3") (pinfunction "OUT_2_P$3") (pintype "output"))
    )
    (net (code "3") (name "ADD2_X_MUX_RI__SP__JSR_ABS") (class "Default")
      (node (ref "CMP11") (pin "2") (pinfunction "1_2") (pintype "input"))
      (node (ref "CMP13") (pin "P$2") (pinfunction "OUT_1_P$2") (pintype "output"))
    )
    (net (code "4") (name "ADDER_X_SPECIAL") (class "Default")
      (node (ref "CMP13") (pin "P$5") (pinfunction "OUT_4_P$5") (pintype "output"))
    )
    (net (code "5") (name "ADDER_Y_SPECIAL") (class "Default")
      (node (ref "CMP13") (pin "P$6") (pinfunction "OUT_5_P$6") (pintype "output"))
    )
    (net (code "6") (name "BUS_CTRL_INSTR") (class "Default")
      (node (ref "CMP31") (pin "INPUT") (pinfunction "OUT_INPUT") (pintype "output"))
    )
    (net (code "7") (name "BUS_DECODE_SPECIAL_REG_0") (class "Default")
      (node (ref "CMP24") (pin "INPUT") (pinfunction "INPUT_INPUT") (pintype "input"))
    )
    (net (code "8") (name "BUS_DECODE_SPECIAL_REG_1") (class "Default")
      (node (ref "CMP23") (pin "INPUT") (pinfunction "INPUT_INPUT") (pintype "input"))
    )
    (net (code "9") (name "BUS_H_D") (class "Default")
      (node (ref "CMP19") (pin "INPUT") (pinfunction "INPUT_INPUT") (pintype "input"))
    )
    (net (code "10") (name "BUS_RNX_SPECIALS") (class "Default")
      (node (ref "CMP13") (pin "INPUT") (pinfunction "INPUT_INPUT") (pintype "input"))
    )
    (net (code "11") (name "BUS_SPECIAL_REG_CTRL0") (class "Default")
      (node (ref "CMP56") (pin "INPUT") (pinfunction "OUT_INPUT") (pintype "output"))
    )
    (net (code "12") (name "BUS_SPECIAL_REG_CTRL1") (class "Default")
      (node (ref "CMP3") (pin "INPUT") (pinfunction "OUT_INPUT") (pintype "output"))
    )
    (net (code "13") (name "BUS_STATE") (class "Default")
      (node (ref "CMP18") (pin "INPUT") (pinfunction "INPUT_INPUT") (pintype "input"))
    )
    (net (code "14") (name "FLAG_F2_N") (class "Default")
      (node (ref "CMP23") (pin "P$3") (pinfunction "OUT_2_P$3") (pintype "output"))
      (node (ref "CMP67") (pin "P$1") (pinfunction "1_P$1") (pintype "input"))
    )
    (net (code "15") (name "H_0") (class "Default")
      (node (ref "CMP19") (pin "P$1") (pinfunction "OUT_0_P$1") (pintype "output"))
      (node (ref "CMP32") (pin "P$1") (pinfunction "0_P$1") (pintype "input"))
    )
    (net (code "16") (name "H_1") (class "Default")
      (node (ref "CMP19") (pin "P$2") (pinfunction "OUT_1_P$2") (pintype "output"))
      (node (ref "CMP32") (pin "P$2") (pinfunction "1_P$2") (pintype "input"))
    )
    (net (code "17") (name "H_2") (class "Default")
      (node (ref "CMP19") (pin "P$3") (pinfunction "OUT_2_P$3") (pintype "output"))
      (node (ref "CMP32") (pin "P$3") (pinfunction "2_P$3") (pintype "input"))
    )
    (net (code "18") (name "H_3") (class "Default")
      (node (ref "CMP19") (pin "P$4") (pinfunction "OUT_3_P$4") (pintype "output"))
      (node (ref "CMP32") (pin "P$4") (pinfunction "3_P$4") (pintype "input"))
    )
    (net (code "19") (name "H_4") (class "Default")
      (node (ref "CMP19") (pin "P$5") (pinfunction "OUT_4_P$5") (pintype "output"))
      (node (ref "CMP6") (pin "IN") (pinfunction "IN_IN") (pintype "input"))
    )
    (net (code "20") (name "H_4_N") (class "Default")
      (node (ref "CMP15") (pin "P$3") (pinfunction "3_P$3") (pintype "input"))
      (node (ref "CMP6") (pin "N") (pinfunction "N_N") (pintype "output"))
    )
    (net (code "21") (name "H_5") (class "Default")
      (node (ref "CMP19") (pin "P$6") (pinfunction "OUT_5_P$6") (pintype "output"))
      (node (ref "CMP35") (pin "P$2") (pinfunction "2_P$2") (pintype "input"))
    )
    (net (code "22") (name "H_6") (class "Default")
      (node (ref "CMP19") (pin "P$7") (pinfunction "OUT_6_P$7") (pintype "output"))
    )
    (net (code "23") (name "H_7") (class "Default")
      (node (ref "CMP19") (pin "P$8") (pinfunction "OUT_7_P$8") (pintype "output"))
    )
    (net (code "24") (name "H_8") (class "Default")
      (node (ref "CMP19") (pin "P$9") (pinfunction "OUT_8_P$9") (pintype "output"))
    )
    (net (code "25") (name "H_9") (class "Default")
      (node (ref "CMP19") (pin "P$10") (pinfunction "OUT_9_P$10") (pintype "output"))
    )
    (net (code "26") (name "H_10") (class "Default")
      (node (ref "CMP19") (pin "P$11") (pinfunction "OUT_10_P$11") (pintype "output"))
    )
    (net (code "27") (name "H_11") (class "Default")
      (node (ref "CMP19") (pin "P$12") (pinfunction "OUT_11_P$12") (pintype "output"))
    )
    (net (code "28") (name "H_12") (class "Default")
      (node (ref "CMP19") (pin "P$13") (pinfunction "OUT_12_P$13") (pintype "output"))
    )
    (net (code "29") (name "H_13") (class "Default")
      (node (ref "CMP19") (pin "P$14") (pinfunction "OUT_13_P$14") (pintype "output"))
    )
    (net (code "30") (name "H_14") (class "Default")
      (node (ref "CMP19") (pin "P$15") (pinfunction "OUT_14_P$15") (pintype "output"))
    )
    (net (code "31") (name "H_15") (class "Default")
      (node (ref "CMP19") (pin "P$16") (pinfunction "OUT_15_P$16") (pintype "output"))
    )
    (net (code "32") (name "H_COUNT_DOWN_SHIFT") (class "Default")
      (node (ref "CMP15") (pin "OUT_P") (pinfunction "P_OUT_P") (pintype "output"))
      (node (ref "CMP3") (pin "P$1") (pinfunction "IN_0_P$1") (pintype "input"))
    )
    (net (code "33") (name "H_COUNT_IS_15") (class "Default")
      (node (ref "CMP32") (pin "OUT_P") (pinfunction "P_OUT_P") (pintype "output"))
      (node (ref "CMP33") (pin "P$1") (pinfunction "1_P$1") (pintype "input"))
    )
    (net (code "34") (name "H_COUNT_IS_15_N") (class "Default")
      (node (ref "CMP32") (pin "OUT_M") (pinfunction "N_OUT_M") (pintype "output"))
      (node (ref "CMP39") (pin "P$1") (pinfunction "A0_P$1") (pintype "input"))
    )
    (net (code "35") (name "IS_END") (class "Default")
      (node (ref "CMP22") (pin "IN") (pinfunction "IN_IN") (pintype "input"))
      (node (ref "CMP23") (pin "P$9") (pinfunction "OUT_8_P$9") (pintype "output"))
      (node (ref "CMP59") (pin "P$1") (pinfunction "1_P$1") (pintype "input"))
      (node (ref "CMP60") (pin "P$3") (pinfunction "3_P$3") (pintype "input"))
    )
    (net (code "36") (name "IS_END_N") (class "Default")
      (node (ref "CMP10") (pin "P$7") (pinfunction "D0_P$7") (pintype "input"))
      (node (ref "CMP22") (pin "N") (pinfunction "N_N") (pintype "output"))
    )
    (net (code "37") (name "IS_NOT_INTERRUPTING_END") (class "Default")
      (node (ref "CMP23") (pin "P$16") (pinfunction "OUT_15_P$16") (pintype "output"))
      (node (ref "CMP30") (pin "2") (pinfunction "1_2") (pintype "input"))
    )
    (net (code "38") (name "IS_STATE_0_1") (class "Default")
      (node (ref "CMP12") (pin "OUT_P") (pinfunction "P_OUT_P") (pintype "output"))
      (node (ref "CMP44") (pin "P$4") (pinfunction "B1_P$4") (pintype "input"))
    )
    (net (code "39") (name "IS_STATE_0_1_N") (class "Default")
      (node (ref "CMP12") (pin "OUT_M") (pinfunction "N_OUT_M") (pintype "output"))
      (node (ref "CMP46") (pin "P$4") (pinfunction "B1_P$4") (pintype "input"))
    )
    (net (code "40") (name "IS_STATE_0_4_6") (class "Default")
      (node (ref "CMP20") (pin "P$4") (pinfunction "B1_P$4") (pintype "input"))
      (node (ref "CMP36") (pin "OUT_P") (pinfunction "P_OUT_P") (pintype "output"))
    )
    (net (code "41") (name "IS_STATE_4_6") (class "Default")
      (node (ref "CMP10") (pin "P$5") (pinfunction "C0_P$5") (pintype "input"))
      (node (ref "CMP42") (pin "P$2") (pinfunction "A1_P$2") (pintype "input"))
      (node (ref "CMP43") (pin "OUT_P") (pinfunction "P_OUT_P") (pintype "output"))
    )
    (net (code "42") (name "NEXT_ADDR_MUX_ADD2") (class "Default")
      (node (ref "CMP1") (pin "P$2") (pinfunction "1_P$2") (pintype "input"))
      (node (ref "CMP11") (pin "OUT_P") (pinfunction "P_OUT_P") (pintype "output"))
      (node (ref "CMP56") (pin "P$9") (pinfunction "IN_8_P$9") (pintype "input"))
    )
    (net (code "43") (name "NEXT_ADDR_MUX_ADD2__SET_A") (class "Default")
      (node (ref "CMP10") (pin "OUT_P") (pinfunction "P_OUT_P") (pintype "output"))
      (node (ref "CMP11") (pin "5") (pinfunction "4_5") (pintype "input"))
    )
    (net (code "44") (name "NEXT_ADDR_MUX_ADD2__SET_A_OPTIONS") (class "Default")
      (node (ref "CMP10") (pin "P$2") (pinfunction "A1_P$2") (pintype "input"))
      (node (ref "CMP10") (pin "P$3") (pinfunction "B0_P$3") (pintype "input"))
      (node (ref "CMP9") (pin "OUT_P") (pinfunction "P_OUT_P") (pintype "output"))
    )
    (net (code "45") (name "NEXT_ADDR_MUX_PC") (class "Default")
      (node (ref "CMP1") (pin "OUT_M") (pinfunction "N_OUT_M") (pintype "output"))
      (node (ref "CMP56") (pin "P$7") (pinfunction "IN_6_P$7") (pintype "input"))
    )
    (net (code "46") (name "NEXT_ADDR_MUX_READ_WORD") (class "Default")
      (node (ref "CMP1") (pin "P$1") (pinfunction "0_P$1") (pintype "input"))
      (node (ref "CMP16") (pin "OUT_P") (pinfunction "P_OUT_P") (pintype "output"))
      (node (ref "CMP56") (pin "P$8") (pinfunction "IN_7_P$8") (pintype "input"))
    )
    (net (code "47") (name "NEXT_ADDR_MUX_RI") (class "Default")
      (node (ref "CMP1") (pin "P$3") (pinfunction "2_P$3") (pintype "input"))
      (node (ref "CMP20") (pin "OUT_P") (pinfunction "P_OUT_P") (pintype "output"))
      (node (ref "CMP56") (pin "P$10") (pinfunction "IN_9_P$10") (pintype "input"))
    )
    (net (code "48") (name "NEXT_ADDR_MUX_RI__SP") (class "Default")
      (node (ref "CMP13") (pin "P$4") (pinfunction "OUT_3_P$4") (pintype "output"))
      (node (ref "CMP20") (pin "P$1") (pinfunction "A0_P$1") (pintype "input"))
      (node (ref "CMP20") (pin "P$2") (pinfunction "A1_P$2") (pintype "input"))
    )
    (net (code "49") (name "NEXT_F_HOLD") (class "Default")
      (node (ref "CMP31") (pin "P$2") (pinfunction "IN_1_P$2") (pintype "input"))
      (node (ref "CMP57") (pin "OUT_M") (pinfunction "N_OUT_M") (pintype "output"))
    )
    (net (code "50") (name "NEXT_F_LOAD") (class "Default")
      (node (ref "CMP31") (pin "P$1") (pinfunction "IN_0_P$1") (pintype "input"))
      (node (ref "CMP57") (pin "OUT_P") (pinfunction "P_OUT_P") (pintype "output"))
    )
    (net (code "51") (name "NEXT_H_MUX_A_ABS_MSB") (class "Default")
      (node (ref "CMP3") (pin "P$11") (pinfunction "IN_10_P$11") (pintype "input"))
      (node (ref "CMP34") (pin "OUT_P") (pinfunction "P_OUT_P") (pintype "output"))
      (node (ref "CMP38") (pin "3") (pinfunction "2_3") (pintype "input"))
    )
    (net (code "52") (name "NEXT_H_MUX_A_ADD2") (class "Default")
      (node (ref "CMP3") (pin "P$12") (pinfunction "IN_11_P$12") (pintype "input"))
      (node (ref "CMP38") (pin "1") (pinfunction "0_1") (pintype "input"))
      (node (ref "CMP8") (pin "OUT_P") (pinfunction "P_OUT_P") (pintype "output"))
    )
    (net (code "53") (name "NEXT_H_MUX_A_ADD2__SET_A") (class "Default")
      (node (ref "CMP46") (pin "OUT_P") (pinfunction "P_OUT_P") (pintype "output"))
      (node (ref "CMP8") (pin "P$1") (pinfunction "A2_P$1") (pintype "input"))
    )
    (net (code "54") (name "NEXT_H_MUX_A_R1") (class "Default")
      (node (ref "CMP3") (pin "P$10") (pinfunction "IN_9_P$10") (pintype "input"))
      (node (ref "CMP33") (pin "OUT_P") (pinfunction "P_OUT_P") (pintype "output"))
      (node (ref "CMP38") (pin "4") (pinfunction "3_4") (pintype "input"))
    )
    (net (code "55") (name "NEXT_H_MUX_A_SXT_RD_DATA") (class "Default")
      (node (ref "CMP3") (pin "P$9") (pinfunction "IN_8_P$9") (pintype "input"))
      (node (ref "CMP37") (pin "OUT_P") (pinfunction "P_OUT_P") (pintype "output"))
      (node (ref "CMP38") (pin "2") (pinfunction "1_2") (pintype "input"))
    )
    (net (code "56") (name "NEXT_H_MUX_A_SXT_RD_DATA__EXCL") (class "Default")
      (node (ref "CMP2") (pin "OUT_P") (pinfunction "P_OUT_P") (pintype "output"))
    )
    (net (code "57") (name "NEXT_H_MUX_A_SXT_RD_DATA__EXCL_N") (class "Default")
      (node (ref "CMP2") (pin "OUT_M") (pinfunction "N_OUT_M") (pintype "output"))
      (node (ref "CMP37") (pin "P$3") (pinfunction "B0_P$3") (pintype "input"))
    )
    (net (code "58") (name "NEXT_H_MUX_B_A") (class "Default")
      (node (ref "CMP3") (pin "P$3") (pinfunction "IN_2_P$3") (pintype "input"))
      (node (ref "CMP38") (pin "OUT_P") (pinfunction "P_OUT_P") (pintype "output"))
      (node (ref "CMP49") (pin "1") (pinfunction "0_1") (pintype "input"))
    )
    (net (code "59") (name "NEXT_H_MUX_B_CLEAR") (class "Default")
      (node (ref "CMP48") (pin "OUT_P") (pinfunction "P_OUT_P") (pintype "output"))
      (node (ref "CMP49") (pin "4") (pinfunction "3_4") (pintype "input"))
    )
    (net (code "60") (name "NEXT_H_MUX_B_HOLD") (class "Default")
      (node (ref "CMP3") (pin "P$2") (pinfunction "IN_1_P$2") (pintype "input"))
      (node (ref "CMP49") (pin "OUT_M") (pinfunction "N_OUT_M") (pintype "output"))
    )
    (net (code "61") (name "NEXT_H_MUX_B_SHIFT_REG_VAL") (class "Default")
      (node (ref "CMP3") (pin "P$4") (pinfunction "IN_3_P$4") (pintype "input"))
      (node (ref "CMP35") (pin "OUT_P") (pinfunction "P_OUT_P") (pintype "output"))
      (node (ref "CMP49") (pin "2") (pinfunction "1_2") (pintype "input"))
    )
    (net (code "62") (name "NEXT_H_MUX_B_SHIFT_UPDATE") (class "Default")
      (node (ref "CMP3") (pin "P$5") (pinfunction "IN_4_P$5") (pintype "input"))
      (node (ref "CMP40") (pin "OUT_P") (pinfunction "P_OUT_P") (pintype "output"))
      (node (ref "CMP49") (pin "3") (pinfunction "2_3") (pintype "input"))
    )
    (net (code "63") (name "NEXT_H_MUX_B_SHIFT_UPDATE__SET_A") (class "Default")
      (node (ref "CMP39") (pin "OUT_P") (pinfunction "P_OUT_P") (pintype "output"))
      (node (ref "CMP40") (pin "4") (pinfunction "3_4") (pintype "input"))
    )
    (net (code "64") (name "NEXT_INSTR_MUX_F") (class "Default")
      (node (ref "CMP31") (pin "P$5") (pinfunction "IN_4_P$5") (pintype "input"))
      (node (ref "CMP59") (pin "OUT_P") (pinfunction "P_OUT_P") (pintype "output"))
      (node (ref "CMP61") (pin "P$3") (pinfunction "2_P$3") (pintype "input"))
    )
    (net (code "65") (name "NEXT_INSTR_MUX_F_N") (class "Default")
      (node (ref "CMP59") (pin "OUT_M") (pinfunction "M_OUT_M") (pintype "output"))
      (node (ref "CMP60") (pin "P$2") (pinfunction "2_P$2") (pintype "input"))
    )
    (net (code "66") (name "NEXT_INSTR_MUX_F__OPTIONS") (class "Default")
      (node (ref "CMP58") (pin "OUT_P") (pinfunction "P_OUT_P") (pintype "output"))
      (node (ref "CMP59") (pin "P$2") (pinfunction "2_P$2") (pintype "input"))
    )
    (net (code "67") (name "NEXT_INSTR_MUX_HOLD") (class "Default")
      (node (ref "CMP31") (pin "P$6") (pinfunction "IN_5_P$6") (pintype "input"))
      (node (ref "CMP61") (pin "OUT_M") (pinfunction "N_OUT_M") (pintype "output"))
    )
    (net (code "68") (name "NEXT_INSTR_MUX_READ_DATA") (class "Default")
      (node (ref "CMP31") (pin "P$4") (pinfunction "IN_3_P$4") (pintype "input"))
      (node (ref "CMP60") (pin "OUT_P") (pinfunction "P_OUT_P") (pintype "output"))
      (node (ref "CMP61") (pin "P$2") (pinfunction "1_P$2") (pintype "input"))
    )
    (net (code "69") (name "NEXT_PC_MUX_ADD2") (class "Default")
      (node (ref "CMP30") (pin "OUT_P") (pinfunction "P_OUT_P") (pintype "output"))
      (node (ref "CMP54") (pin "P$2") (pinfunction "1_P$2") (pintype "input"))
      (node (ref "CMP56") (pin "P$5") (pinfunction "IN_4_P$5") (pintype "input"))
    )
    (net (code "70") (name "NEXT_PC_MUX_ADD2__0_OPTIONS") (class "Default")
      (node (ref "CMP29") (pin "OUT_P") (pinfunction "P_OUT_P") (pintype "output"))
      (node (ref "CMP44") (pin "P$1") (pinfunction "A0_P$1") (pintype "input"))
    )
    (net (code "71") (name "NEXT_PC_MUX_ADD2__MEM_OPTIONS") (class "Default")
      (node (ref "CMP44") (pin "P$3") (pinfunction "B0_P$3") (pintype "input"))
      (node (ref "CMP5") (pin "OUT_P") (pinfunction "P_OUT_P") (pintype "output"))
    )
    (net (code "72") (name "NEXT_PC_MUX_ADD2__SET_A") (class "Default")
      (node (ref "CMP30") (pin "4") (pinfunction "3_4") (pintype "input"))
      (node (ref "CMP44") (pin "OUT_P") (pinfunction "P_OUT_P") (pintype "output"))
    )
    (net (code "73") (name "NEXT_PC_MUX_HOLD") (class "Default")
      (node (ref "CMP54") (pin "OUT_M") (pinfunction "N_OUT_M") (pintype "output"))
      (node (ref "CMP56") (pin "P$3") (pinfunction "IN_2_P$3") (pintype "input"))
    )
    (net (code "74") (name "NEXT_PC_MUX_H_AND_DATA") (class "Default")
      (node (ref "CMP52") (pin "OUT_P") (pinfunction "P_OUT_P") (pintype "output"))
      (node (ref "CMP54") (pin "P$1") (pinfunction "0_P$1") (pintype "input"))
      (node (ref "CMP56") (pin "P$4") (pinfunction "IN_3_P$4") (pintype "input"))
    )
    (net (code "75") (name "NEXT_PC_MUX_VECTOR") (class "Default")
      (node (ref "CMP53") (pin "OUT_P") (pinfunction "P_OUT_P") (pintype "output"))
      (node (ref "CMP54") (pin "P$3") (pinfunction "2_P$3") (pintype "input"))
      (node (ref "CMP56") (pin "P$6") (pinfunction "IN_5_P$6") (pintype "input"))
    )
    (net (code "76") (name "NEXT_SP_ADD2__B") (class "Default")
      (node (ref "CMP42") (pin "OUT_P") (pinfunction "P_OUT_P") (pintype "output"))
      (node (ref "CMP47") (pin "4") (pinfunction "3_4") (pintype "input"))
    )
    (net (code "77") (name "NEXT_SP_MUX_ADD2") (class "Default")
      (node (ref "CMP47") (pin "OUT_P") (pinfunction "P_OUT_P") (pintype "output"))
      (node (ref "CMP56") (pin "P$11") (pinfunction "IN_10_P$11") (pintype "input"))
    )
    (net (code "78") (name "NEXT_SP_MUX_ADD2__SET_A_OPTIONS") (class "Default")
      (node (ref "CMP41") (pin "OUT_P") (pinfunction "P_OUT_P") (pintype "output"))
      (node (ref "CMP42") (pin "P$7") (pinfunction "D0_P$7") (pintype "input"))
    )
    (net (code "79") (name "NEXT_SP_MUX_HOLD") (class "Default")
      (node (ref "CMP47") (pin "OUT_M") (pinfunction "N_OUT_M") (pintype "output"))
      (node (ref "CMP56") (pin "P$12") (pinfunction "IN_11_P$12") (pintype "input"))
    )
    (net (code "80") (name "NEXT_WR_DATA_MUX_PC_RA_LSB__7") (class "Default")
      (node (ref "CMP21") (pin "OUT_P") (pinfunction "P_OUT_P") (pintype "output"))
      (node (ref "CMP26") (pin "P$1") (pinfunction "A0_P$1") (pintype "input"))
    )
    (net (code "81") (name "NEXT_WR_DATA_MUX_PC_RA_MSB__7") (class "Default")
      (node (ref "CMP27") (pin "OUT_M") (pinfunction "N_OUT_M") (pintype "output"))
      (node (ref "CMP28") (pin "P$1") (pinfunction "A0_P$1") (pintype "input"))
    )
    (net (code "82") (name "NEXT_WR_DATA_MUX_PC_RN_LSB") (class "Default")
      (node (ref "CMP26") (pin "OUT_P") (pinfunction "P_OUT_P") (pintype "output"))
      (node (ref "CMP3") (pin "P$7") (pinfunction "IN_6_P$7") (pintype "input"))
    )
    (net (code "83") (name "NEXT_WR_DATA_MUX_PC_RN_MSB") (class "Default")
      (node (ref "CMP28") (pin "OUT_P") (pinfunction "P_OUT_P") (pintype "output"))
      (node (ref "CMP3") (pin "P$8") (pinfunction "IN_7_P$8") (pintype "input"))
    )
    (net (code "84") (name "NEXT_WR_DATA_MUX_PS") (class "Default")
      (node (ref "CMP17") (pin "OUT_P") (pinfunction "P_OUT_P") (pintype "output"))
      (node (ref "CMP27") (pin "P$3") (pinfunction "2_P$3") (pintype "input"))
      (node (ref "CMP3") (pin "P$6") (pinfunction "IN_5_P$6") (pintype "input"))
    )
    (net (code "85") (name "NEXT_WR_DATA_MUX_PS_N") (class "Default")
      (node (ref "CMP17") (pin "OUT_M") (pinfunction "N_OUT_M") (pintype "output"))
      (node (ref "CMP21") (pin "P$3") (pinfunction "3_P$3") (pintype "input"))
    )
    (net (code "86") (name "NON_RESET_TRAP") (class "Default")
      (node (ref "CMP67") (pin "OUT_P") (pinfunction "P_OUT_P") (pintype "output"))
      (node (ref "CMP9") (pin "4") (pinfunction "3_4") (pintype "input"))
    )
    (net (code "87") (name "Net-(CMP31-IN_10)") (class "Default")
      (node (ref "CMP31") (pin "P$10") (pinfunction "IN_9_P$10") (pintype "input"))
      (node (ref "CMP31") (pin "P$11") (pinfunction "IN_10_P$11") (pintype "input"))
      (node (ref "CMP31") (pin "P$12") (pinfunction "IN_11_P$12") (pintype "input"))
      (node (ref "CMP31") (pin "P$13") (pinfunction "IN_12_P$13") (pintype "input"))
      (node (ref "CMP31") (pin "P$14") (pinfunction "IN_13_P$14") (pintype "input"))
      (node (ref "CMP31") (pin "P$15") (pinfunction "IN_14_P$15") (pintype "input"))
      (node (ref "CMP31") (pin "P$16") (pinfunction "IN_15_P$16") (pintype "input"))
      (node (ref "CMP31") (pin "P$7") (pinfunction "IN_6_P$7") (pintype "input"))
      (node (ref "CMP31") (pin "P$8") (pinfunction "IN_7_P$8") (pintype "input"))
      (node (ref "CMP31") (pin "P$9") (pinfunction "IN_8_P$9") (pintype "input"))
    )
    (net (code "88") (name "Net-(CMP56-IN_12)") (class "Default")
      (node (ref "CMP56") (pin "P$13") (pinfunction "IN_12_P$13") (pintype "input"))
      (node (ref "CMP56") (pin "P$14") (pinfunction "IN_13_P$14") (pintype "input"))
      (node (ref "CMP56") (pin "P$15") (pinfunction "IN_14_P$15") (pintype "input"))
      (node (ref "CMP56") (pin "P$16") (pinfunction "IN_15_P$16") (pintype "input"))
    )
    (net (code "89") (name "OPCODE_IS_ABSOLUTE_GROUP") (class "Default")
      (node (ref "CMP10") (pin "P$6") (pinfunction "C1_P$6") (pintype "input"))
      (node (ref "CMP16") (pin "P$1") (pinfunction "1_P$1") (pintype "input"))
      (node (ref "CMP24") (pin "P$12") (pinfunction "OUT_11_P$12") (pintype "output"))
      (node (ref "CMP34") (pin "P$4") (pinfunction "B1_P$4") (pintype "input"))
      (node (ref "CMP46") (pin "P$3") (pinfunction "B0_P$3") (pintype "input"))
      (node (ref "CMP5") (pin "4") (pinfunction "3_4") (pintype "input"))
    )
    (net (code "90") (name "OPCODE_IS_ADD_SP") (class "Default")
      (node (ref "CMP23") (pin "P$7") (pinfunction "OUT_6_P$7") (pintype "output"))
      (node (ref "CMP29") (pin "3") (pinfunction "2_3") (pintype "input"))
      (node (ref "CMP42") (pin "P$3") (pinfunction "B0_P$3") (pintype "input"))
    )
    (net (code "91") (name "OPCODE_IS_ANDI_ORI_PS_LDI_X") (class "Default")
      (node (ref "CMP23") (pin "P$8") (pinfunction "OUT_7_P$8") (pintype "output"))
      (node (ref "CMP5") (pin "2") (pinfunction "1_2") (pintype "input"))
    )
    (net (code "92") (name "OPCODE_IS_BXX") (class "Default")
      (node (ref "CMP23") (pin "P$6") (pinfunction "OUT_5_P$6") (pintype "output"))
      (node (ref "CMP29") (pin "2") (pinfunction "1_2") (pintype "input"))
    )
    (net (code "93") (name "OPCODE_IS_BXX_STATE_2") (class "Default")
      (node (ref "CMP11") (pin "4") (pinfunction "3_4") (pintype "input"))
      (node (ref "CMP23") (pin "P$12") (pinfunction "OUT_11_P$12") (pintype "output"))
      (node (ref "CMP30") (pin "3") (pinfunction "2_3") (pintype "input"))
    )
    (net (code "94") (name "OPCODE_IS_INDIRECT_POSTINC") (class "Default")
      (node (ref "CMP2") (pin "P$1") (pinfunction "A2_P$1") (pintype "input"))
      (node (ref "CMP20") (pin "P$3") (pinfunction "B0_P$3") (pintype "input"))
      (node (ref "CMP24") (pin "P$3") (pinfunction "OUT_2_P$3") (pintype "output"))
      (node (ref "CMP58") (pin "2") (pinfunction "1_2") (pintype "input"))
      (node (ref "CMP8") (pin "P$2") (pinfunction "A1_P$2") (pintype "input"))
    )
    (net (code "95") (name "OPCODE_IS_JMP_ABS") (class "Default")
      (node (ref "CMP23") (pin "P$10") (pinfunction "OUT_9_P$10") (pintype "output"))
      (node (ref "CMP29") (pin "5") (pinfunction "4_5") (pintype "input"))
      (node (ref "CMP52") (pin "P$4") (pinfunction "B1_P$4") (pintype "input"))
    )
    (net (code "96") (name "OPCODE_IS_JMP_R0") (class "Default")
      (node (ref "CMP23") (pin "P$5") (pinfunction "OUT_4_P$5") (pintype "output"))
      (node (ref "CMP29") (pin "1") (pinfunction "0_1") (pintype "input"))
    )
    (net (code "97") (name "OPCODE_IS_JSR_ABS") (class "Default")
      (node (ref "CMP14") (pin "P$2") (pinfunction "1_P$2") (pintype "input"))
      (node (ref "CMP24") (pin "P$6") (pinfunction "OUT_5_P$6") (pintype "output"))
      (node (ref "CMP25") (pin "1") (pinfunction "0_1") (pintype "input"))
      (node (ref "CMP34") (pin "P$1") (pinfunction "A0_P$1") (pintype "input"))
      (node (ref "CMP5") (pin "3") (pinfunction "2_3") (pintype "input"))
    )
    (net (code "98") (name "OPCODE_IS_JSR_R0") (class "Default")
      (node (ref "CMP14") (pin "P$1") (pinfunction "0_P$1") (pintype "input"))
      (node (ref "CMP24") (pin "P$5") (pinfunction "OUT_4_P$5") (pintype "output"))
      (node (ref "CMP25") (pin "2") (pinfunction "1_2") (pintype "input"))
      (node (ref "CMP41") (pin "3") (pinfunction "2_3") (pintype "input"))
      (node (ref "CMP9") (pin "1") (pinfunction "0_1") (pintype "input"))
    )
    (net (code "99") (name "OPCODE_IS_JSR_X_STATE_7") (class "Default")
      (node (ref "CMP23") (pin "P$4") (pinfunction "OUT_3_P$4") (pintype "output"))
      (node (ref "CMP30") (pin "1") (pinfunction "0_1") (pintype "input"))
    )
    (net (code "100") (name "OPCODE_IS_MOVE_SP_R0") (class "Default")
      (node (ref "CMP23") (pin "P$2") (pinfunction "OUT_1_P$2") (pintype "output"))
      (node (ref "CMP42") (pin "P$5") (pinfunction "C0_P$5") (pintype "input"))
    )
    (net (code "101") (name "OPCODE_IS_MUL_SQRT_DIV") (class "Default")
      (node (ref "CMP2") (pin "P$2") (pinfunction "A1_P$2") (pintype "input"))
      (node (ref "CMP23") (pin "P$15") (pinfunction "OUT_14_P$15") (pintype "output"))
      (node (ref "CMP48") (pin "P$1") (pinfunction "1_P$1") (pintype "input"))
    )
    (net (code "102") (name "OPCODE_IS_POP_RA_PS") (class "Default")
      (node (ref "CMP24") (pin "P$14") (pinfunction "OUT_13_P$14") (pintype "output"))
      (node (ref "CMP41") (pin "1") (pinfunction "0_1") (pintype "input"))
      (node (ref "CMP58") (pin "5") (pinfunction "4_5") (pintype "input"))
    )
    (net (code "103") (name "OPCODE_IS_PUSH_PS") (class "Default")
      (node (ref "CMP17") (pin "P$4") (pinfunction "B1_P$4") (pintype "input"))
      (node (ref "CMP24") (pin "P$9") (pinfunction "OUT_8_P$9") (pintype "output"))
      (node (ref "CMP41") (pin "5") (pinfunction "4_5") (pintype "input"))
      (node (ref "CMP58") (pin "4") (pinfunction "3_4") (pintype "input"))
      (node (ref "CMP9") (pin "3") (pinfunction "2_3") (pintype "input"))
    )
    (net (code "104") (name "OPCODE_IS_PUSH_RA") (class "Default")
      (node (ref "CMP24") (pin "P$1") (pinfunction "OUT_0_P$1") (pintype "output"))
      (node (ref "CMP25") (pin "3") (pinfunction "2_3") (pintype "input"))
      (node (ref "CMP26") (pin "P$3") (pinfunction "B0_P$3") (pintype "input"))
      (node (ref "CMP27") (pin "P$1") (pinfunction "0_P$1") (pintype "input"))
      (node (ref "CMP28") (pin "P$3") (pinfunction "B0_P$3") (pintype "input"))
      (node (ref "CMP41") (pin "4") (pinfunction "3_4") (pintype "input"))
      (node (ref "CMP58") (pin "1") (pinfunction "0_1") (pintype "input"))
      (node (ref "CMP9") (pin "2") (pinfunction "1_2") (pintype "input"))
    )
    (net (code "105") (name "OPCODE_IS_RET_RETI") (class "Default")
      (node (ref "CMP23") (pin "P$11") (pinfunction "OUT_10_P$11") (pintype "output"))
      (node (ref "CMP37") (pin "P$1") (pinfunction "A0_P$1") (pintype "input"))
      (node (ref "CMP41") (pin "2") (pinfunction "1_2") (pintype "input"))
      (node (ref "CMP52") (pin "P$1") (pinfunction "A0_P$1") (pintype "input"))
    )
    (net (code "106") (name "OPCODE_IS_SHIFT_BIT") (class "Default")
      (node (ref "CMP24") (pin "P$10") (pinfunction "OUT_9_P$10") (pintype "output"))
      (node (ref "CMP29") (pin "4") (pinfunction "3_4") (pintype "input"))
      (node (ref "CMP35") (pin "P$3") (pinfunction "3_P$3") (pintype "input"))
    )
    (net (code "107") (name "OPCODE_IS_SHIFT_XX") (class "Default")
      (node (ref "CMP15") (pin "P$1") (pinfunction "1_P$1") (pintype "input"))
      (node (ref "CMP24") (pin "P$16") (pinfunction "OUT_15_P$16") (pintype "output"))
      (node (ref "CMP39") (pin "P$3") (pinfunction "B0_P$3") (pintype "input"))
    )
    (net (code "108") (name "OPCODE_IS_STACK_GROUP") (class "Default")
      (node (ref "CMP23") (pin "P$1") (pinfunction "OUT_0_P$1") (pintype "output"))
      (node (ref "CMP42") (pin "P$1") (pinfunction "A0_P$1") (pintype "input"))
    )
    (net (code "109") (name "OPCODE_IS_STACK_REL_GROUP") (class "Default")
      (node (ref "CMP10") (pin "P$8") (pinfunction "D1_P$8") (pintype "input"))
      (node (ref "CMP24") (pin "P$11") (pinfunction "OUT_10_P$11") (pintype "output"))
      (node (ref "CMP46") (pin "P$2") (pinfunction "A1_P$2") (pintype "input"))
      (node (ref "CMP5") (pin "1") (pinfunction "0_1") (pintype "input"))
      (node (ref "CMP58") (pin "3") (pinfunction "2_3") (pintype "input"))
      (node (ref "CMP7") (pin "IN") (pinfunction "IN_IN") (pintype "input"))
    )
    (net (code "110") (name "OPCODE_IS_STACK_REL_GROUP_N") (class "Default")
      (node (ref "CMP3") (pin "P$15") (pinfunction "IN_14_P$15") (pintype "input"))
      (node (ref "CMP7") (pin "N") (pinfunction "N_N") (pintype "output"))
    )
    (net (code "111") (name "OPCODE_IS_STACK_REL_STATE_2") (class "Default")
      (node (ref "CMP24") (pin "P$15") (pinfunction "OUT_14_P$15") (pintype "output"))
      (node (ref "CMP57") (pin "P$2") (pinfunction "A1_P$2") (pintype "input"))
    )
    (net (code "112") (name "OPCODE_IS_TRAP") (class "Default")
      (node (ref "CMP14") (pin "P$3") (pinfunction "2_P$3") (pintype "input"))
      (node (ref "CMP24") (pin "P$8") (pinfunction "OUT_7_P$8") (pintype "output"))
      (node (ref "CMP25") (pin "4") (pinfunction "3_4") (pintype "input"))
      (node (ref "CMP45") (pin "P$1") (pinfunction "1_P$1") (pintype "input"))
      (node (ref "CMP67") (pin "P$2") (pinfunction "2_P$2") (pintype "input"))
    )
    (net (code "113") (name "OPCODE_IS_TRAP_JSR_X") (class "Default")
      (node (ref "CMP14") (pin "OUT_P") (pinfunction "P_OUT_P") (pintype "output"))
      (node (ref "CMP26") (pin "P$8") (pinfunction "D1_P$8") (pintype "input"))
      (node (ref "CMP28") (pin "P$8") (pinfunction "D1_P$8") (pintype "input"))
      (node (ref "CMP3") (pin "P$13") (pinfunction "IN_12_P$13") (pintype "input"))
    )
    (net (code "114") (name "OPCODE_IS_TRAP_JSR_X_N") (class "Default")
      (node (ref "CMP14") (pin "OUT_M") (pinfunction "N_OUT_M") (pintype "output"))
      (node (ref "CMP21") (pin "P$2") (pinfunction "2_P$2") (pintype "input"))
      (node (ref "CMP3") (pin "P$14") (pinfunction "IN_13_P$14") (pintype "input"))
    )
    (net (code "115") (name "OPCODE_IS_TRAP_JSR_X_PUSH_RA") (class "Default")
      (node (ref "CMP25") (pin "OUT_P") (pinfunction "P_OUT_P") (pintype "output"))
    )
    (net (code "116") (name "OPCODE_IS_TRAP_JSR_X_PUSH_RA_N") (class "Default")
      (node (ref "CMP25") (pin "OUT_M") (pinfunction "N_OUT_M") (pintype "output"))
      (node (ref "CMP26") (pin "P$5") (pinfunction "C0_P$5") (pintype "input"))
    )
    (net (code "117") (name "RESET_SIGNAL") (class "Default")
      (node (ref "CMP53") (pin "P$2") (pinfunction "2_P$2") (pintype "input"))
    )
    (net (code "118") (name "SIZE_BIT_IS_BYTE") (class "Default")
      (node (ref "CMP21") (pin "P$1") (pinfunction "1_P$1") (pintype "input"))
      (node (ref "CMP24") (pin "P$2") (pinfunction "OUT_1_P$2") (pintype "output"))
      (node (ref "CMP27") (pin "P$2") (pinfunction "1_P$2") (pintype "input"))
    )
    (net (code "119") (name "STATE_0") (class "Default")
      (node (ref "CMP10") (pin "P$4") (pinfunction "B1_P$4") (pintype "input"))
      (node (ref "CMP12") (pin "P$2") (pinfunction "A1_P$2") (pintype "input"))
      (node (ref "CMP17") (pin "P$3") (pinfunction "B0_P$3") (pintype "input"))
      (node (ref "CMP18") (pin "P$1") (pinfunction "OUT_0_P$1") (pintype "output"))
      (node (ref "CMP28") (pin "P$4") (pinfunction "B1_P$4") (pintype "input"))
      (node (ref "CMP28") (pin "P$7") (pinfunction "D0_P$7") (pintype "input"))
      (node (ref "CMP36") (pin "P$3") (pinfunction "2_P$3") (pintype "input"))
      (node (ref "CMP37") (pin "P$4") (pinfunction "B1_P$4") (pintype "input"))
      (node (ref "CMP4") (pin "IN") (pinfunction "IN_IN") (pintype "input"))
      (node (ref "CMP42") (pin "P$6") (pinfunction "C1_P$6") (pintype "input"))
      (node (ref "CMP42") (pin "P$8") (pinfunction "D1_P$8") (pintype "input"))
      (node (ref "CMP44") (pin "P$2") (pinfunction "A1_P$2") (pintype "input"))
      (node (ref "CMP48") (pin "P$2") (pinfunction "2_P$2") (pintype "input"))
      (node (ref "CMP57") (pin "P$1") (pinfunction "A2_P$1") (pintype "input"))
    )
    (net (code "120") (name "STATE_0_N") (class "Default")
      (node (ref "CMP4") (pin "N") (pinfunction "N_N") (pintype "output"))
      (node (ref "CMP46") (pin "P$1") (pinfunction "A0_P$1") (pintype "input"))
    )
    (net (code "121") (name "STATE_1") (class "Default")
      (node (ref "CMP12") (pin "P$1") (pinfunction "A2_P$1") (pintype "input"))
      (node (ref "CMP16") (pin "P$2") (pinfunction "2_P$2") (pintype "input"))
      (node (ref "CMP18") (pin "P$2") (pinfunction "OUT_1_P$2") (pintype "output"))
      (node (ref "CMP34") (pin "P$2") (pinfunction "A1_P$2") (pintype "input"))
      (node (ref "CMP34") (pin "P$3") (pinfunction "B0_P$3") (pintype "input"))
      (node (ref "CMP35") (pin "P$1") (pinfunction "1_P$1") (pintype "input"))
      (node (ref "CMP52") (pin "P$3") (pinfunction "B0_P$3") (pintype "input"))
    )
    (net (code "122") (name "STATE_2") (class "Default")
      (node (ref "CMP15") (pin "P$2") (pinfunction "2_P$2") (pintype "input"))
      (node (ref "CMP18") (pin "P$3") (pinfunction "OUT_2_P$3") (pintype "output"))
      (node (ref "CMP39") (pin "P$4") (pinfunction "B1_P$4") (pintype "input"))
      (node (ref "CMP42") (pin "P$4") (pinfunction "B1_P$4") (pintype "input"))
    )
    (net (code "123") (name "STATE_3") (class "Default")
      (node (ref "CMP18") (pin "P$4") (pinfunction "OUT_3_P$4") (pintype "output"))
    )
    (net (code "124") (name "STATE_4") (class "Default")
      (node (ref "CMP18") (pin "P$5") (pinfunction "OUT_4_P$5") (pintype "output"))
      (node (ref "CMP36") (pin "P$2") (pinfunction "1_P$2") (pintype "input"))
      (node (ref "CMP37") (pin "P$2") (pinfunction "A1_P$2") (pintype "input"))
      (node (ref "CMP43") (pin "P$1") (pinfunction "A2_P$1") (pintype "input"))
    )
    (net (code "125") (name "STATE_5") (class "Default")
      (node (ref "CMP18") (pin "P$6") (pinfunction "OUT_5_P$6") (pintype "output"))
      (node (ref "CMP52") (pin "P$2") (pinfunction "A1_P$2") (pintype "input"))
    )
    (net (code "126") (name "STATE_6") (class "Default")
      (node (ref "CMP10") (pin "P$1") (pinfunction "A0_P$1") (pintype "input"))
      (node (ref "CMP18") (pin "P$7") (pinfunction "OUT_6_P$7") (pintype "output"))
      (node (ref "CMP26") (pin "P$4") (pinfunction "B1_P$4") (pintype "input"))
      (node (ref "CMP26") (pin "P$7") (pinfunction "D0_P$7") (pintype "input"))
      (node (ref "CMP36") (pin "P$1") (pinfunction "0_P$1") (pintype "input"))
      (node (ref "CMP43") (pin "P$2") (pinfunction "A1_P$2") (pintype "input"))
      (node (ref "CMP50") (pin "P$1") (pinfunction "0_P$1") (pintype "input"))
    )
    (net (code "127") (name "STATE_7") (class "Default")
      (node (ref "CMP18") (pin "P$8") (pinfunction "OUT_7_P$8") (pintype "output"))
      (node (ref "CMP45") (pin "P$2") (pinfunction "2_P$2") (pintype "input"))
      (node (ref "CMP50") (pin "P$2") (pinfunction "1_P$2") (pintype "input"))
    )
    (net (code "128") (name "STATE_8") (class "Default")
      (node (ref "CMP18") (pin "P$9") (pinfunction "OUT_8_P$9") (pintype "output"))
      (node (ref "CMP47") (pin "1") (pinfunction "0_1") (pintype "input"))
    )
    (net (code "129") (name "STATE_9") (class "Default")
      (node (ref "CMP18") (pin "P$10") (pinfunction "OUT_9_P$10") (pintype "output"))
      (node (ref "CMP50") (pin "P$3") (pinfunction "2_P$3") (pintype "input"))
    )
    (net (code "130") (name "STATE_10") (class "Default")
      (node (ref "CMP18") (pin "P$11") (pinfunction "OUT_10_P$11") (pintype "output"))
      (node (ref "CMP40") (pin "1") (pinfunction "0_1") (pintype "input"))
    )
    (net (code "131") (name "STATE_11") (class "Default")
      (node (ref "CMP18") (pin "P$12") (pinfunction "OUT_11_P$12") (pintype "output"))
      (node (ref "CMP40") (pin "2") (pinfunction "1_2") (pintype "input"))
    )
    (net (code "132") (name "STATE_12") (class "Default")
      (node (ref "CMP18") (pin "P$13") (pinfunction "OUT_12_P$13") (pintype "output"))
      (node (ref "CMP40") (pin "3") (pinfunction "2_3") (pintype "input"))
    )
    (net (code "133") (name "STATE_13") (class "Default")
      (node (ref "CMP18") (pin "P$14") (pinfunction "OUT_13_P$14") (pintype "output"))
      (node (ref "CMP33") (pin "P$2") (pinfunction "2_P$2") (pintype "input"))
      (node (ref "CMP39") (pin "P$2") (pinfunction "A1_P$2") (pintype "input"))
    )
    (net (code "134") (name "STATE_14") (class "Default")
      (node (ref "CMP18") (pin "P$15") (pinfunction "OUT_14_P$15") (pintype "output"))
    )
    (net (code "135") (name "STATE_15") (class "Default")
      (node (ref "CMP11") (pin "1") (pinfunction "0_1") (pintype "input"))
      (node (ref "CMP18") (pin "P$16") (pinfunction "OUT_15_P$16") (pintype "output"))
      (node (ref "CMP28") (pin "P$5") (pinfunction "C0_P$5") (pintype "input"))
      (node (ref "CMP28") (pin "P$6") (pinfunction "C1_P$6") (pintype "input"))
      (node (ref "CMP47") (pin "2") (pinfunction "1_2") (pintype "input"))
    )
    (net (code "136") (name "TAKE_EXCEPTION") (class "Default")
      (node (ref "CMP24") (pin "P$13") (pinfunction "OUT_12_P$13") (pintype "output"))
      (node (ref "CMP31") (pin "P$3") (pinfunction "IN_2_P$3") (pintype "input"))
      (node (ref "CMP61") (pin "P$1") (pinfunction "0_P$1") (pintype "input"))
      (node (ref "CMP62") (pin "IN") (pinfunction "IN_IN") (pintype "input"))
    )
    (net (code "137") (name "TAKE_EXCEPTION_N") (class "Default")
      (node (ref "CMP59") (pin "P$3") (pinfunction "3_P$3") (pintype "input"))
      (node (ref "CMP60") (pin "P$1") (pinfunction "1_P$1") (pintype "input"))
      (node (ref "CMP62") (pin "N") (pinfunction "N_N") (pintype "output"))
    )
    (net (code "138") (name "TRAP_STATE_7") (class "Default")
      (node (ref "CMP11") (pin "3") (pinfunction "2_3") (pintype "input"))
      (node (ref "CMP17") (pin "P$1") (pinfunction "A0_P$1") (pintype "input"))
      (node (ref "CMP17") (pin "P$2") (pinfunction "A1_P$2") (pintype "input"))
      (node (ref "CMP45") (pin "OUT_P") (pinfunction "P_OUT_P") (pintype "output"))
      (node (ref "CMP47") (pin "3") (pinfunction "2_3") (pintype "input"))
      (node (ref "CMP53") (pin "P$1") (pinfunction "1_P$1") (pintype "input"))
    )
    (net (code "139") (name "VECTOR_CODE_0") (class "Default")
      (node (ref "CMP23") (pin "P$13") (pinfunction "OUT_12_P$13") (pintype "output"))
      (node (ref "CMP56") (pin "P$2") (pinfunction "IN_1_P$2") (pintype "input"))
    )
    (net (code "140") (name "VECTOR_CODE_1") (class "Default")
      (node (ref "CMP23") (pin "P$14") (pinfunction "OUT_13_P$14") (pintype "output"))
      (node (ref "CMP56") (pin "P$1") (pinfunction "IN_0_P$1") (pintype "input"))
    )
    (net (code "141") (name "WE") (class "Default")
      (node (ref "CMP50") (pin "OUT_P") (pinfunction "P_OUT_P") (pintype "output"))
    )
    (net (code "142") (name "WILL_BE_STATE_6") (class "Default")
      (node (ref "CMP24") (pin "P$7") (pinfunction "OUT_6_P$7") (pintype "output"))
      (node (ref "CMP26") (pin "P$6") (pinfunction "C1_P$6") (pintype "input"))
    )
    (net (code "143") (name "WILL_BE_STATE_7") (class "Default")
      (node (ref "CMP24") (pin "P$4") (pinfunction "OUT_3_P$4") (pintype "output"))
      (node (ref "CMP26") (pin "P$2") (pinfunction "A1_P$2") (pintype "input"))
      (node (ref "CMP28") (pin "P$2") (pinfunction "A1_P$2") (pintype "input"))
    )
    (net (code "144") (name "unconnected-(CMP1-P-PadOUT_P)") (class "Default")
      (node (ref "CMP1") (pin "OUT_P") (pinfunction "P_OUT_P") (pintype "output"))
    )
    (net (code "145") (name "unconnected-(CMP3-IN_15-PadP$16)") (class "Default")
      (node (ref "CMP3") (pin "P$16") (pinfunction "IN_15_P$16") (pintype "input"))
    )
    (net (code "146") (name "unconnected-(CMP4-PadP)") (class "Default")
      (node (ref "CMP4") (pin "P") (pinfunction "P_P") (pintype "output"))
    )
    (net (code "147") (name "unconnected-(CMP5-N-PadOUT_M)") (class "Default")
      (node (ref "CMP5") (pin "OUT_M") (pinfunction "N_OUT_M") (pintype "output"))
    )
    (net (code "148") (name "unconnected-(CMP6-PadP)") (class "Default")
      (node (ref "CMP6") (pin "P") (pinfunction "P_P") (pintype "output"))
    )
    (net (code "149") (name "unconnected-(CMP7-PadP)") (class "Default")
      (node (ref "CMP7") (pin "P") (pinfunction "P_P") (pintype "output"))
    )
    (net (code "150") (name "unconnected-(CMP8-N-PadOUT_M)") (class "Default")
      (node (ref "CMP8") (pin "OUT_M") (pinfunction "N_OUT_M") (pintype "output"))
    )
    (net (code "151") (name "unconnected-(CMP9-N-PadOUT_M)") (class "Default")
      (node (ref "CMP9") (pin "OUT_M") (pinfunction "N_OUT_M") (pintype "output"))
    )
    (net (code "152") (name "unconnected-(CMP10-N-PadOUT_M)") (class "Default")
      (node (ref "CMP10") (pin "OUT_M") (pinfunction "N_OUT_M") (pintype "output"))
    )
    (net (code "153") (name "unconnected-(CMP11-N-PadOUT_M)") (class "Default")
      (node (ref "CMP11") (pin "OUT_M") (pinfunction "N_OUT_M") (pintype "output"))
    )
    (net (code "154") (name "unconnected-(CMP13-OUT_6-PadP$7)") (class "Default")
      (node (ref "CMP13") (pin "P$7") (pinfunction "OUT_6_P$7") (pintype "output"))
    )
    (net (code "155") (name "unconnected-(CMP13-OUT_7-PadP$8)") (class "Default")
      (node (ref "CMP13") (pin "P$8") (pinfunction "OUT_7_P$8") (pintype "output"))
    )
    (net (code "156") (name "unconnected-(CMP13-OUT_8-PadP$9)") (class "Default")
      (node (ref "CMP13") (pin "P$9") (pinfunction "OUT_8_P$9") (pintype "output"))
    )
    (net (code "157") (name "unconnected-(CMP13-OUT_9-PadP$10)") (class "Default")
      (node (ref "CMP13") (pin "P$10") (pinfunction "OUT_9_P$10") (pintype "output"))
    )
    (net (code "158") (name "unconnected-(CMP13-OUT_10-PadP$11)") (class "Default")
      (node (ref "CMP13") (pin "P$11") (pinfunction "OUT_10_P$11") (pintype "output"))
    )
    (net (code "159") (name "unconnected-(CMP13-OUT_11-PadP$12)") (class "Default")
      (node (ref "CMP13") (pin "P$12") (pinfunction "OUT_11_P$12") (pintype "output"))
    )
    (net (code "160") (name "unconnected-(CMP13-OUT_12-PadP$13)") (class "Default")
      (node (ref "CMP13") (pin "P$13") (pinfunction "OUT_12_P$13") (pintype "output"))
    )
    (net (code "161") (name "unconnected-(CMP13-OUT_13-PadP$14)") (class "Default")
      (node (ref "CMP13") (pin "P$14") (pinfunction "OUT_13_P$14") (pintype "output"))
    )
    (net (code "162") (name "unconnected-(CMP13-OUT_14-PadP$15)") (class "Default")
      (node (ref "CMP13") (pin "P$15") (pinfunction "OUT_14_P$15") (pintype "output"))
    )
    (net (code "163") (name "unconnected-(CMP13-OUT_15-PadP$16)") (class "Default")
      (node (ref "CMP13") (pin "P$16") (pinfunction "OUT_15_P$16") (pintype "output"))
    )
    (net (code "164") (name "unconnected-(CMP15-M-PadOUT_M)") (class "Default")
      (node (ref "CMP15") (pin "OUT_M") (pinfunction "M_OUT_M") (pintype "output"))
    )
    (net (code "165") (name "unconnected-(CMP16-N-PadOUT_M)") (class "Default")
      (node (ref "CMP16") (pin "OUT_M") (pinfunction "N_OUT_M") (pintype "output"))
    )
    (net (code "166") (name "unconnected-(CMP20-N-PadOUT_M)") (class "Default")
      (node (ref "CMP20") (pin "OUT_M") (pinfunction "N_OUT_M") (pintype "output"))
    )
    (net (code "167") (name "unconnected-(CMP21-M-PadOUT_M)") (class "Default")
      (node (ref "CMP21") (pin "OUT_M") (pinfunction "M_OUT_M") (pintype "output"))
    )
    (net (code "168") (name "unconnected-(CMP22-PadP)") (class "Default")
      (node (ref "CMP22") (pin "P") (pinfunction "P_P") (pintype "output"))
    )
    (net (code "169") (name "unconnected-(CMP26-N-PadOUT_M)") (class "Default")
      (node (ref "CMP26") (pin "OUT_M") (pinfunction "N_OUT_M") (pintype "output"))
    )
    (net (code "170") (name "unconnected-(CMP27-P-PadOUT_P)") (class "Default")
      (node (ref "CMP27") (pin "OUT_P") (pinfunction "P_OUT_P") (pintype "output"))
    )
    (net (code "171") (name "unconnected-(CMP28-N-PadOUT_M)") (class "Default")
      (node (ref "CMP28") (pin "OUT_M") (pinfunction "N_OUT_M") (pintype "output"))
    )
    (net (code "172") (name "unconnected-(CMP29-N-PadOUT_M)") (class "Default")
      (node (ref "CMP29") (pin "OUT_M") (pinfunction "N_OUT_M") (pintype "output"))
    )
    (net (code "173") (name "unconnected-(CMP30-N-PadOUT_M)") (class "Default")
      (node (ref "CMP30") (pin "OUT_M") (pinfunction "N_OUT_M") (pintype "output"))
    )
    (net (code "174") (name "unconnected-(CMP33-N-PadOUT_M)") (class "Default")
      (node (ref "CMP33") (pin "OUT_M") (pinfunction "N_OUT_M") (pintype "output"))
    )
    (net (code "175") (name "unconnected-(CMP34-N-PadOUT_M)") (class "Default")
      (node (ref "CMP34") (pin "OUT_M") (pinfunction "N_OUT_M") (pintype "output"))
    )
    (net (code "176") (name "unconnected-(CMP35-M-PadOUT_M)") (class "Default")
      (node (ref "CMP35") (pin "OUT_M") (pinfunction "M_OUT_M") (pintype "output"))
    )
    (net (code "177") (name "unconnected-(CMP36-N-PadOUT_M)") (class "Default")
      (node (ref "CMP36") (pin "OUT_M") (pinfunction "N_OUT_M") (pintype "output"))
    )
    (net (code "178") (name "unconnected-(CMP37-N-PadOUT_M)") (class "Default")
      (node (ref "CMP37") (pin "OUT_M") (pinfunction "N_OUT_M") (pintype "output"))
    )
    (net (code "179") (name "unconnected-(CMP38-N-PadOUT_M)") (class "Default")
      (node (ref "CMP38") (pin "OUT_M") (pinfunction "N_OUT_M") (pintype "output"))
    )
    (net (code "180") (name "unconnected-(CMP39-N-PadOUT_M)") (class "Default")
      (node (ref "CMP39") (pin "OUT_M") (pinfunction "N_OUT_M") (pintype "output"))
    )
    (net (code "181") (name "unconnected-(CMP40-N-PadOUT_M)") (class "Default")
      (node (ref "CMP40") (pin "OUT_M") (pinfunction "N_OUT_M") (pintype "output"))
    )
    (net (code "182") (name "unconnected-(CMP41-N-PadOUT_M)") (class "Default")
      (node (ref "CMP41") (pin "OUT_M") (pinfunction "N_OUT_M") (pintype "output"))
    )
    (net (code "183") (name "unconnected-(CMP42-N-PadOUT_M)") (class "Default")
      (node (ref "CMP42") (pin "OUT_M") (pinfunction "N_OUT_M") (pintype "output"))
    )
    (net (code "184") (name "unconnected-(CMP43-N-PadOUT_M)") (class "Default")
      (node (ref "CMP43") (pin "OUT_M") (pinfunction "N_OUT_M") (pintype "output"))
    )
    (net (code "185") (name "unconnected-(CMP44-N-PadOUT_M)") (class "Default")
      (node (ref "CMP44") (pin "OUT_M") (pinfunction "N_OUT_M") (pintype "output"))
    )
    (net (code "186") (name "unconnected-(CMP45-N-PadOUT_M)") (class "Default")
      (node (ref "CMP45") (pin "OUT_M") (pinfunction "N_OUT_M") (pintype "output"))
    )
    (net (code "187") (name "unconnected-(CMP46-N-PadOUT_M)") (class "Default")
      (node (ref "CMP46") (pin "OUT_M") (pinfunction "N_OUT_M") (pintype "output"))
    )
    (net (code "188") (name "unconnected-(CMP48-N-PadOUT_M)") (class "Default")
      (node (ref "CMP48") (pin "OUT_M") (pinfunction "N_OUT_M") (pintype "output"))
    )
    (net (code "189") (name "unconnected-(CMP49-P-PadOUT_P)") (class "Default")
      (node (ref "CMP49") (pin "OUT_P") (pinfunction "P_OUT_P") (pintype "output"))
    )
    (net (code "190") (name "unconnected-(CMP50-N-PadOUT_M)") (class "Default")
      (node (ref "CMP50") (pin "OUT_M") (pinfunction "N_OUT_M") (pintype "output"))
    )
    (net (code "191") (name "unconnected-(CMP52-N-PadOUT_M)") (class "Default")
      (node (ref "CMP52") (pin "OUT_M") (pinfunction "N_OUT_M") (pintype "output"))
    )
    (net (code "192") (name "unconnected-(CMP53-N-PadOUT_M)") (class "Default")
      (node (ref "CMP53") (pin "OUT_M") (pinfunction "N_OUT_M") (pintype "output"))
    )
    (net (code "193") (name "unconnected-(CMP54-P-PadOUT_P)") (class "Default")
      (node (ref "CMP54") (pin "OUT_P") (pinfunction "P_OUT_P") (pintype "output"))
    )
    (net (code "194") (name "unconnected-(CMP58-N-PadOUT_M)") (class "Default")
      (node (ref "CMP58") (pin "OUT_M") (pinfunction "N_OUT_M") (pintype "output"))
    )
    (net (code "195") (name "unconnected-(CMP60-M-PadOUT_M)") (class "Default")
      (node (ref "CMP60") (pin "OUT_M") (pinfunction "M_OUT_M") (pintype "output"))
    )
    (net (code "196") (name "unconnected-(CMP61-P-PadOUT_P)") (class "Default")
      (node (ref "CMP61") (pin "OUT_P") (pinfunction "P_OUT_P") (pintype "output"))
    )
    (net (code "197") (name "unconnected-(CMP62-PadP)") (class "Default")
      (node (ref "CMP62") (pin "P") (pinfunction "P_P") (pintype "output"))
    )
    (net (code "198") (name "unconnected-(CMP67-N-PadOUT_M)") (class "Default")
      (node (ref "CMP67") (pin "OUT_M") (pinfunction "N_OUT_M") (pintype "output"))
    )
  )
)
